# blinds_v60.net
KiCad netlist of a schematic drawn in EAGLE
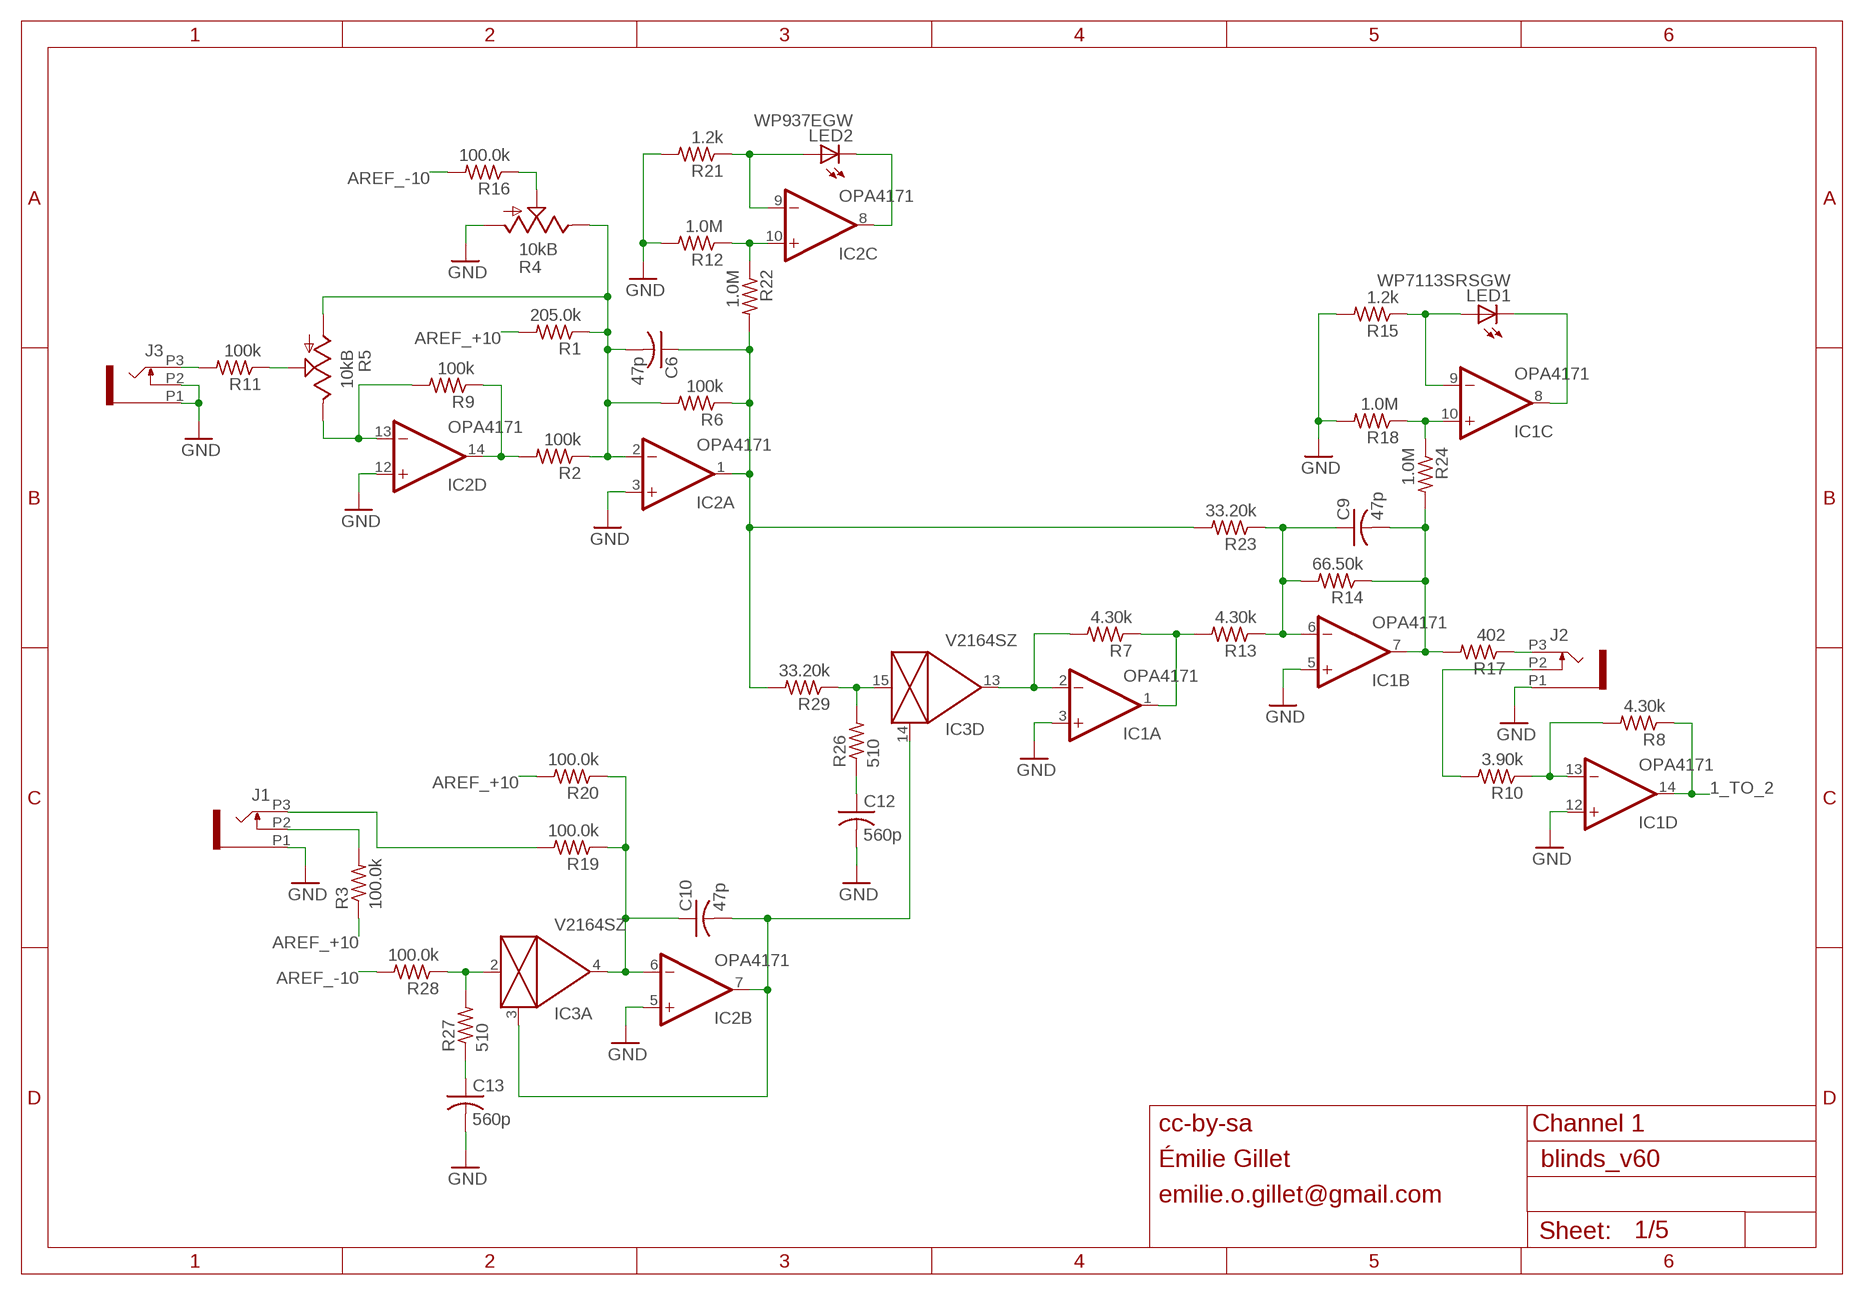
[diagram p0: schematic, sheet 1]
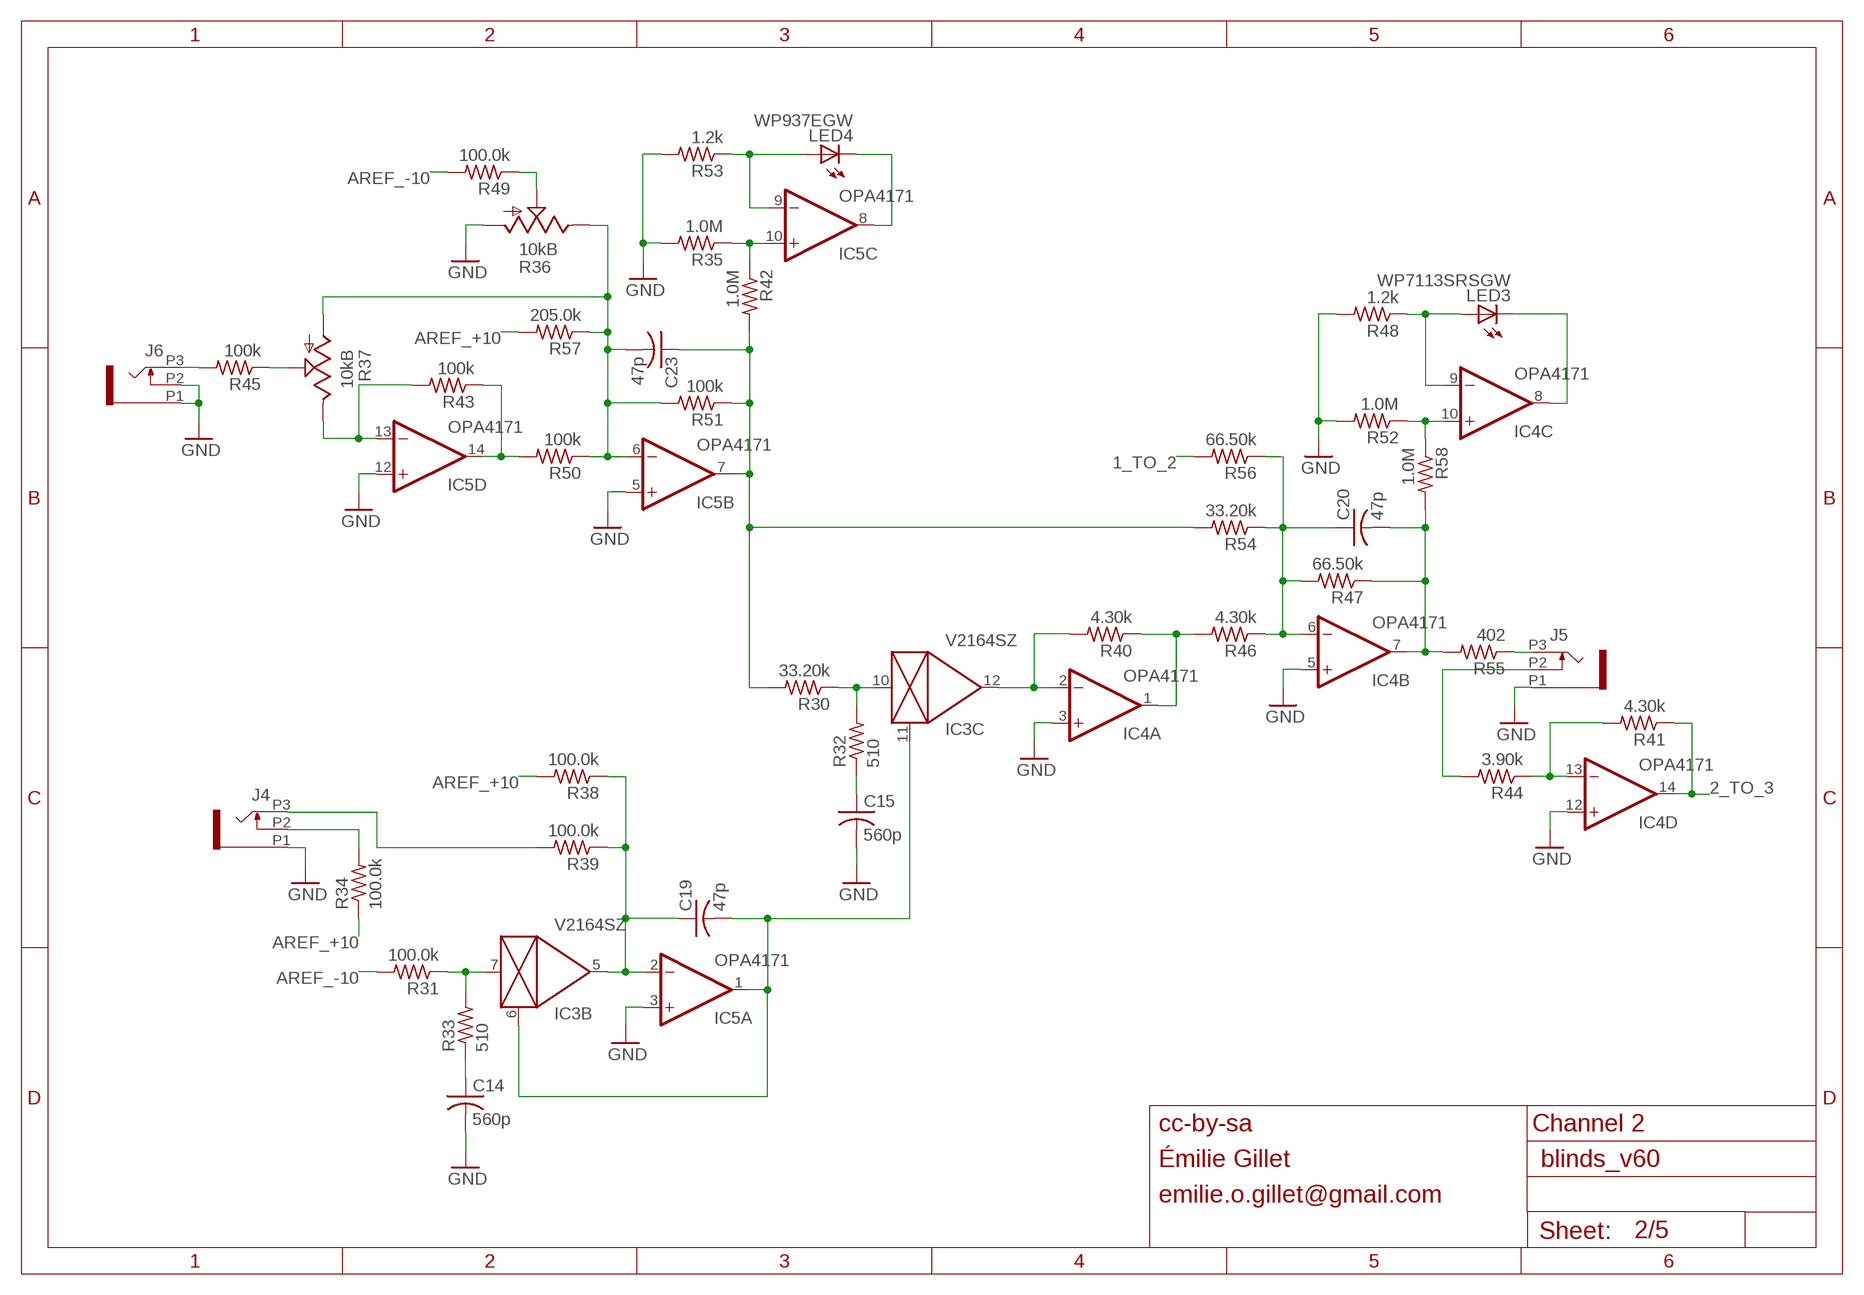
[diagram p1: schematic, sheet 2]
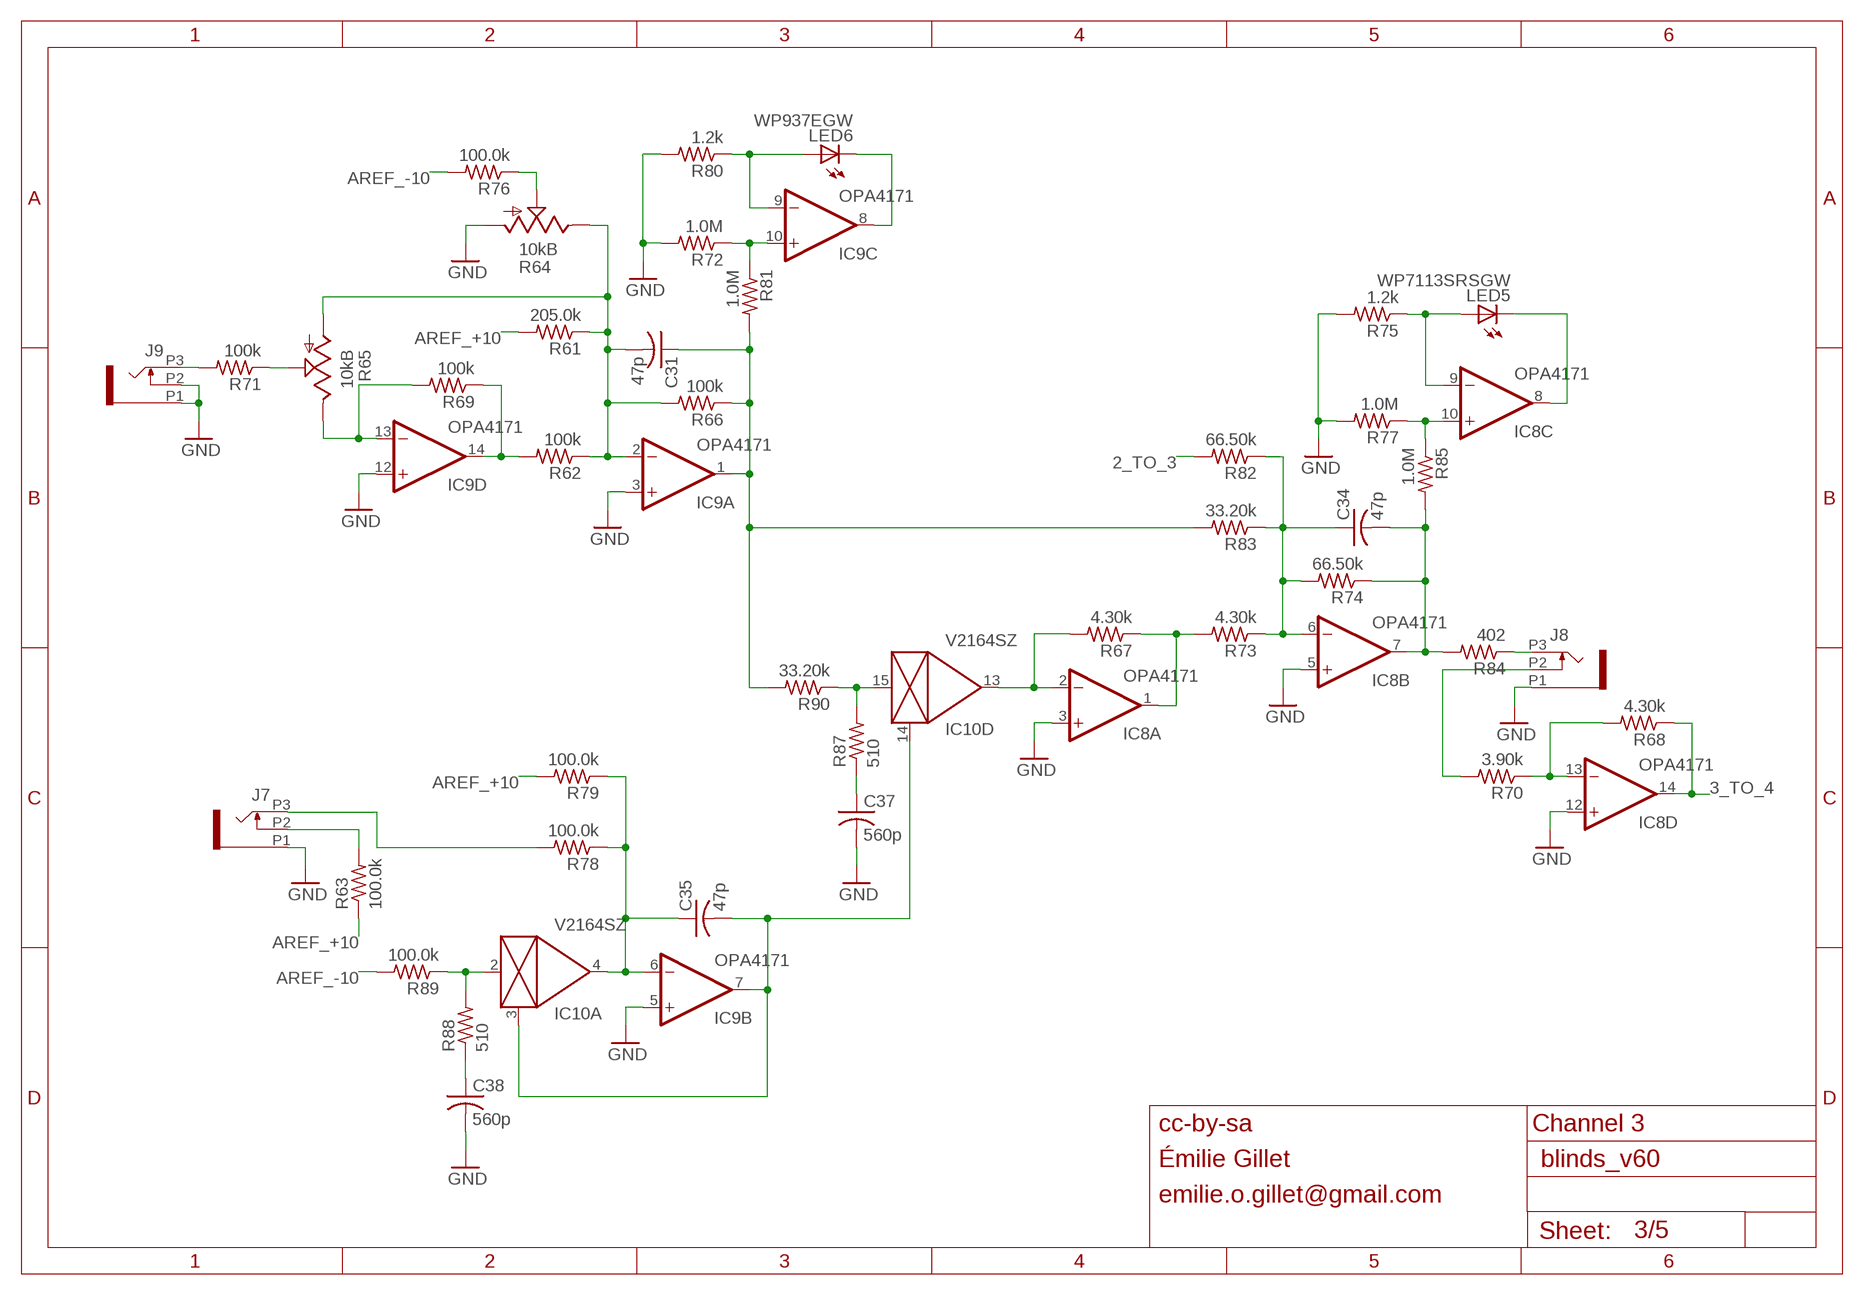
[diagram p2: schematic, sheet 3]
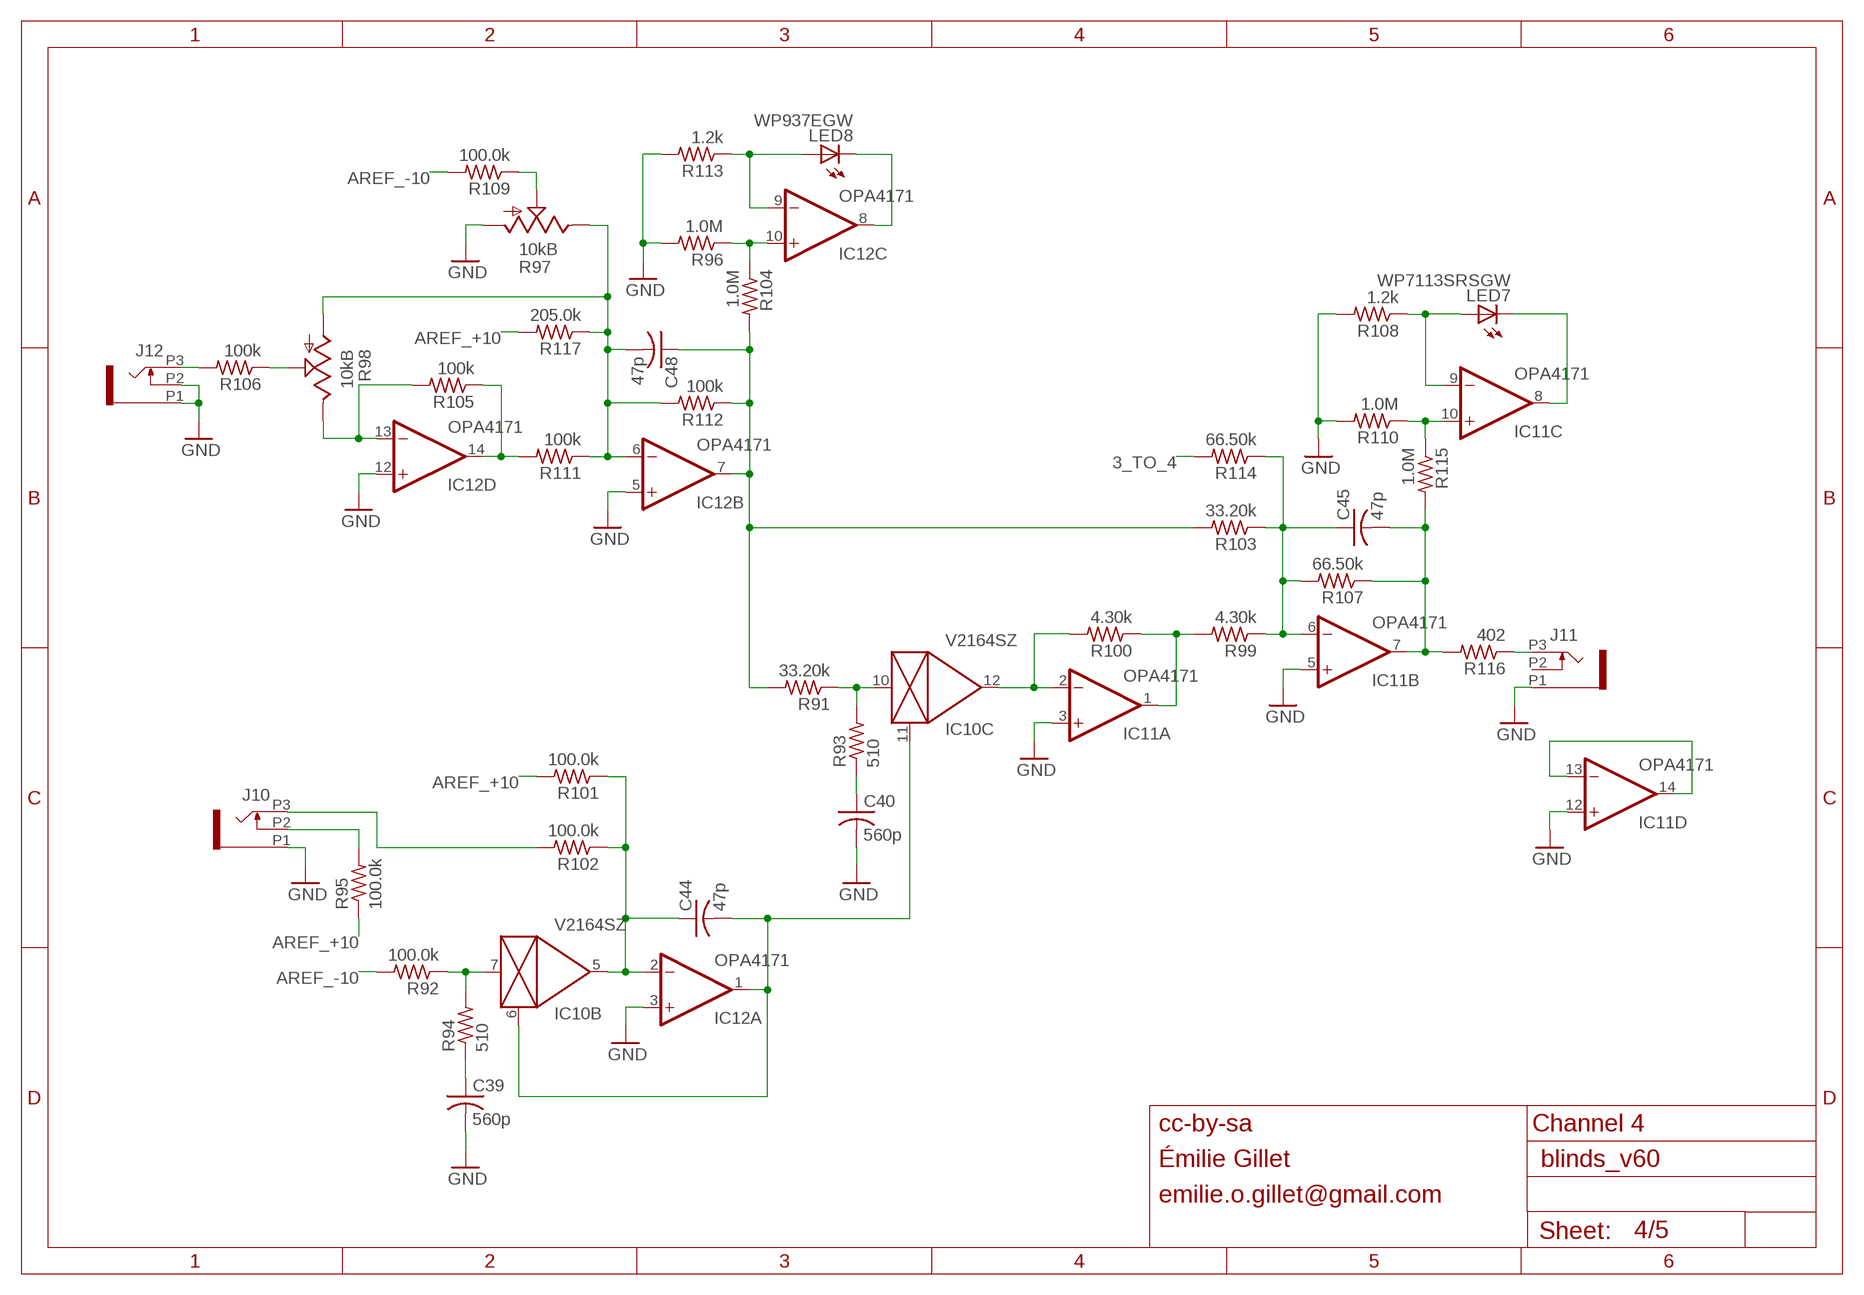
[diagram p3: schematic, sheet 4]
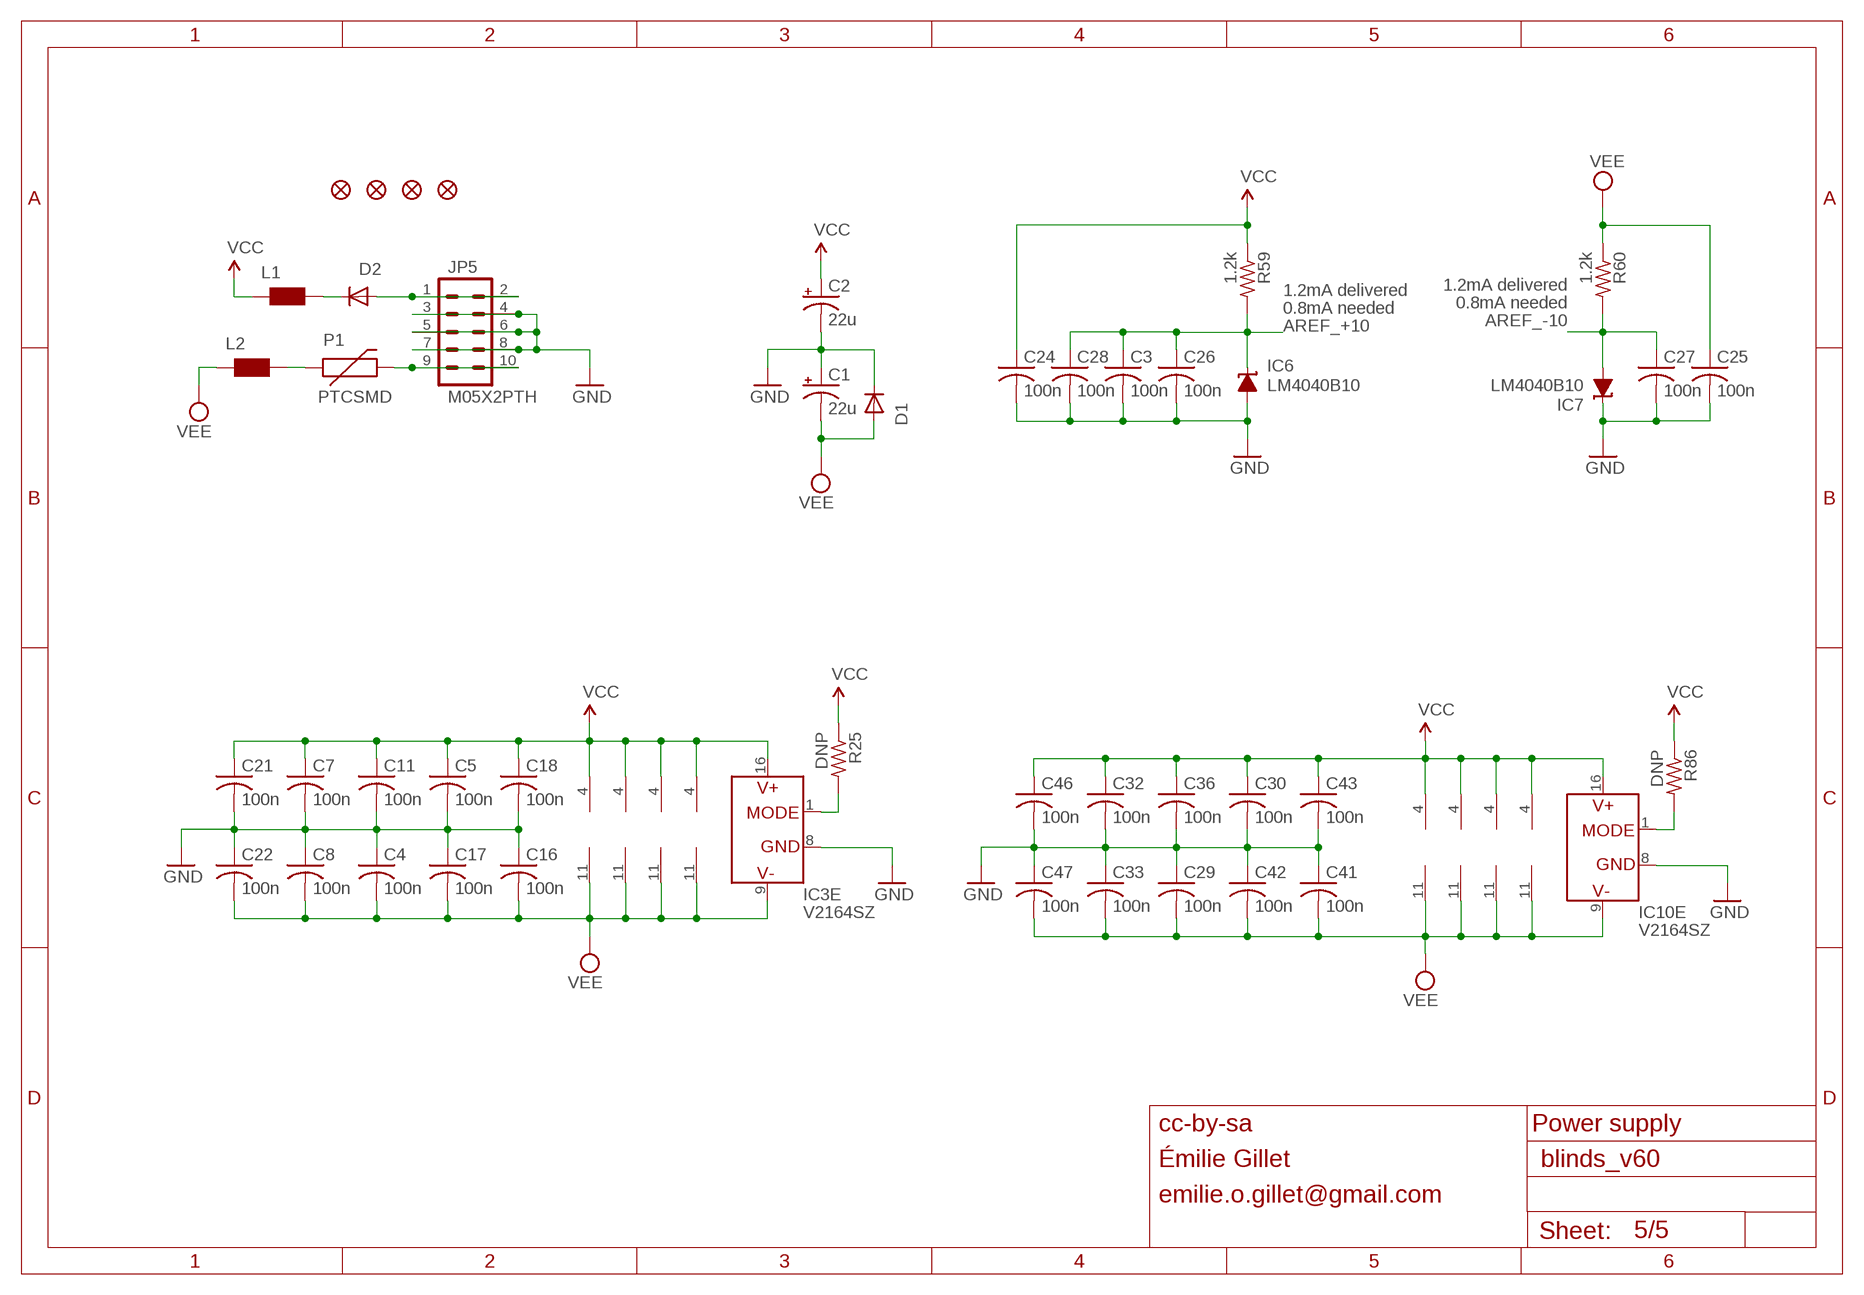
[diagram p4: schematic, sheet 5]

(export (version "E")
  (design (tool "Eeschema 10.0.6"))
  (components
    (comp (ref "C1")
      (value "22u")
      (footprint "eagle-import:PANASONIC_C")
      (libsource (lib "eagle-import") (part "CPOL-USC"))
    )
    (comp (ref "C2")
      (value "22u")
      (footprint "eagle-import:PANASONIC_C")
      (libsource (lib "eagle-import") (part "CPOL-USC"))
    )
    (comp (ref "C3")
      (value "100n")
      (footprint "eagle-import:C0603")
      (libsource (lib "eagle-import") (part "C-USC0603"))
    )
    (comp (ref "C4")
      (value "100n")
      (footprint "eagle-import:C0603")
      (libsource (lib "eagle-import") (part "C-USC0603"))
    )
    (comp (ref "C5")
      (value "100n")
      (footprint "eagle-import:C0603")
      (libsource (lib "eagle-import") (part "C-USC0603"))
    )
    (comp (ref "C7")
      (value "100n")
      (footprint "eagle-import:C0603")
      (libsource (lib "eagle-import") (part "C-USC0603"))
    )
    (comp (ref "C8")
      (value "100n")
      (footprint "eagle-import:C0603")
      (libsource (lib "eagle-import") (part "C-USC0603"))
    )
    (comp (ref "C11")
      (value "100n")
      (footprint "eagle-import:C0603")
      (libsource (lib "eagle-import") (part "C-USC0603"))
    )
    (comp (ref "C16")
      (value "100n")
      (footprint "eagle-import:C0603")
      (libsource (lib "eagle-import") (part "C-USC0603"))
    )
    (comp (ref "C17")
      (value "100n")
      (footprint "eagle-import:C0603")
      (libsource (lib "eagle-import") (part "C-USC0603"))
    )
    (comp (ref "C18")
      (value "100n")
      (footprint "eagle-import:C0603")
      (libsource (lib "eagle-import") (part "C-USC0603"))
    )
    (comp (ref "C21")
      (value "100n")
      (footprint "eagle-import:C0603")
      (libsource (lib "eagle-import") (part "C-USC0603"))
    )
    (comp (ref "C22")
      (value "100n")
      (footprint "eagle-import:C0603")
      (libsource (lib "eagle-import") (part "C-USC0603"))
    )
    (comp (ref "C24")
      (value "100n")
      (footprint "eagle-import:C0603")
      (libsource (lib "eagle-import") (part "C-USC0603"))
    )
    (comp (ref "C25")
      (value "100n")
      (footprint "eagle-import:C0603")
      (libsource (lib "eagle-import") (part "C-USC0603"))
    )
    (comp (ref "C26")
      (value "100n")
      (footprint "eagle-import:C0603")
      (libsource (lib "eagle-import") (part "C-USC0603"))
    )
    (comp (ref "C27")
      (value "100n")
      (footprint "eagle-import:C0603")
      (libsource (lib "eagle-import") (part "C-USC0603"))
    )
    (comp (ref "C28")
      (value "100n")
      (footprint "eagle-import:C0603")
      (libsource (lib "eagle-import") (part "C-USC0603"))
    )
    (comp (ref "C29")
      (value "100n")
      (footprint "eagle-import:C0603")
      (libsource (lib "eagle-import") (part "C-USC0603"))
    )
    (comp (ref "C30")
      (value "100n")
      (footprint "eagle-import:C0603")
      (libsource (lib "eagle-import") (part "C-USC0603"))
    )
    (comp (ref "C32")
      (value "100n")
      (footprint "eagle-import:C0603")
      (libsource (lib "eagle-import") (part "C-USC0603"))
    )
    (comp (ref "C33")
      (value "100n")
      (footprint "eagle-import:C0603")
      (libsource (lib "eagle-import") (part "C-USC0603"))
    )
    (comp (ref "C36")
      (value "100n")
      (footprint "eagle-import:C0603")
      (libsource (lib "eagle-import") (part "C-USC0603"))
    )
    (comp (ref "C41")
      (value "100n")
      (footprint "eagle-import:C0603")
      (libsource (lib "eagle-import") (part "C-USC0603"))
    )
    (comp (ref "C42")
      (value "100n")
      (footprint "eagle-import:C0603")
      (libsource (lib "eagle-import") (part "C-USC0603"))
    )
    (comp (ref "C43")
      (value "100n")
      (footprint "eagle-import:C0603")
      (libsource (lib "eagle-import") (part "C-USC0603"))
    )
    (comp (ref "C46")
      (value "100n")
      (footprint "eagle-import:C0603")
      (libsource (lib "eagle-import") (part "C-USC0603"))
    )
    (comp (ref "C47")
      (value "100n")
      (footprint "eagle-import:C0603")
      (libsource (lib "eagle-import") (part "C-USC0603"))
    )
    (comp (ref "D1")
      (value "1N5819HW")
      (footprint "eagle-import:SOD123")
      (libsource (lib "eagle-import") (part "DIODE-SOD123"))
    )
    (comp (ref "D2")
      (value "1N5819HW")
      (footprint "eagle-import:SOD123")
      (libsource (lib "eagle-import") (part "DIODE-SOD123"))
    )
    (comp (ref "IC1")
      (value "OPA4171")
      (footprint "eagle-import:TSSOP14")
      (libsource (lib "eagle-import") (part "TL074PW"))
    )
    (comp (ref "IC2")
      (value "OPA4171")
      (footprint "eagle-import:TSSOP14")
      (libsource (lib "eagle-import") (part "TL074PW"))
    )
    (comp (ref "IC3")
      (value "V2164SZ")
      (footprint "eagle-import:SOIC16N")
      (libsource (lib "eagle-import") (part "SSM2164S"))
    )
    (comp (ref "IC4")
      (value "OPA4171")
      (footprint "eagle-import:TSSOP14")
      (libsource (lib "eagle-import") (part "TL074PW"))
    )
    (comp (ref "IC5")
      (value "OPA4171")
      (footprint "eagle-import:TSSOP14")
      (libsource (lib "eagle-import") (part "TL074PW"))
    )
    (comp (ref "IC6")
      (value "LM4040B10")
      (footprint "eagle-import:DBZ_R-PDSO-G3")
      (libsource (lib "eagle-import") (part "LM4041DBZB12"))
    )
    (comp (ref "IC7")
      (value "LM4040B10")
      (footprint "eagle-import:DBZ_R-PDSO-G3")
      (libsource (lib "eagle-import") (part "LM4041DBZB12"))
    )
    (comp (ref "IC8")
      (value "OPA4171")
      (footprint "eagle-import:TSSOP14")
      (libsource (lib "eagle-import") (part "TL074PW"))
    )
    (comp (ref "IC9")
      (value "OPA4171")
      (footprint "eagle-import:TSSOP14")
      (libsource (lib "eagle-import") (part "TL074PW"))
    )
    (comp (ref "IC10")
      (value "V2164SZ")
      (footprint "eagle-import:SOIC16N")
      (libsource (lib "eagle-import") (part "SSM2164S"))
    )
    (comp (ref "IC11")
      (value "OPA4171")
      (footprint "eagle-import:TSSOP14")
      (libsource (lib "eagle-import") (part "TL074PW"))
    )
    (comp (ref "IC12")
      (value "OPA4171")
      (footprint "eagle-import:TSSOP14")
      (libsource (lib "eagle-import") (part "TL074PW"))
    )
    (comp (ref "JP1")
      (value "FIDUCIAL1X2")
      (footprint "eagle-import:FIDUCIAL-1X2")
      (libsource (lib "eagle-import") (part "FIDUCIAL1X2"))
    )
    (comp (ref "JP2")
      (value "FIDUCIAL1X2")
      (footprint "eagle-import:FIDUCIAL-1X2")
      (libsource (lib "eagle-import") (part "FIDUCIAL1X2"))
    )
    (comp (ref "JP3")
      (value "FIDUCIAL1X2")
      (footprint "eagle-import:FIDUCIAL-1X2")
      (libsource (lib "eagle-import") (part "FIDUCIAL1X2"))
    )
    (comp (ref "JP4")
      (value "FIDUCIAL1X2")
      (footprint "eagle-import:FIDUCIAL-1X2")
      (libsource (lib "eagle-import") (part "FIDUCIAL1X2"))
    )
    (comp (ref "JP5")
      (value "M05X2PTH")
      (footprint "eagle-import:AVR_ICSP")
      (libsource (lib "eagle-import") (part "M05X2PTH"))
    )
    (comp (ref "L1")
      (value "WE-CBF_0603")
      (footprint "eagle-import:0603")
      (libsource (lib "eagle-import") (part "WE-CBF_0603"))
    )
    (comp (ref "L2")
      (value "WE-CBF_0603")
      (footprint "eagle-import:0603")
      (libsource (lib "eagle-import") (part "WE-CBF_0603"))
    )
    (comp (ref "P1")
      (value "PTCSMD")
      (footprint "eagle-import:PTC-1206")
      (libsource (lib "eagle-import") (part "PTCSMD"))
    )
    (comp (ref "R25")
      (value "DNP")
      (footprint "eagle-import:R0603")
      (libsource (lib "eagle-import") (part "R-US_R0603"))
    )
    (comp (ref "R59")
      (value "1.2k")
      (footprint "eagle-import:R0603")
      (libsource (lib "eagle-import") (part "R-US_R0603"))
    )
    (comp (ref "R60")
      (value "1.2k")
      (footprint "eagle-import:R0603")
      (libsource (lib "eagle-import") (part "R-US_R0603"))
    )
    (comp (ref "R86")
      (value "DNP")
      (footprint "eagle-import:R0603")
      (libsource (lib "eagle-import") (part "R-US_R0603"))
    )
    (comp (ref "C31")
      (value "47p")
      (footprint "eagle-import:C0603")
      (libsource (lib "eagle-import") (part "C-USC0603"))
    )
    (comp (ref "C34")
      (value "47p")
      (footprint "eagle-import:C0603")
      (libsource (lib "eagle-import") (part "C-USC0603"))
    )
    (comp (ref "C35")
      (value "47p")
      (footprint "eagle-import:C0603")
      (libsource (lib "eagle-import") (part "C-USC0603"))
    )
    (comp (ref "C37")
      (value "560p")
      (footprint "eagle-import:C0603")
      (libsource (lib "eagle-import") (part "C-USC0603"))
    )
    (comp (ref "C38")
      (value "560p")
      (footprint "eagle-import:C0603")
      (libsource (lib "eagle-import") (part "C-USC0603"))
    )
    (comp (ref "J7")
      (value "PJ301_THONKICONN6")
      (footprint "eagle-import:WQP_PJ_301M6")
      (libsource (lib "eagle-import") (part "PJ301_THONKICONN6"))
    )
    (comp (ref "J8")
      (value "PJ301_THONKICONN6")
      (footprint "eagle-import:WQP_PJ_301M6")
      (libsource (lib "eagle-import") (part "PJ301_THONKICONN6"))
    )
    (comp (ref "J9")
      (value "PJ301_THONKICONN6")
      (footprint "eagle-import:WQP_PJ_301M6")
      (libsource (lib "eagle-import") (part "PJ301_THONKICONN6"))
    )
    (comp (ref "LED5")
      (value "WP7113SRSGW")
      (footprint "eagle-import:LED5MM")
      (libsource (lib "eagle-import") (part "LED5MM"))
    )
    (comp (ref "LED6")
      (value "WP937EGW")
      (footprint "eagle-import:LED3MM")
      (libsource (lib "eagle-import") (part "LED3MM"))
    )
    (comp (ref "R61")
      (value "205.0k")
      (footprint "eagle-import:R0603")
      (libsource (lib "eagle-import") (part "R-US_R0603"))
    )
    (comp (ref "R62")
      (value "100k")
      (footprint "eagle-import:R0603")
      (libsource (lib "eagle-import") (part "R-US_R0603"))
    )
    (comp (ref "R63")
      (value "100.0k")
      (footprint "eagle-import:R0603")
      (libsource (lib "eagle-import") (part "R-US_R0603"))
    )
    (comp (ref "R64")
      (value "10kB")
      (footprint "eagle-import:ALPS_POT_VERTICAL_PS")
      (libsource (lib "eagle-import") (part "POT_USVERTICAL_PS"))
    )
    (comp (ref "R65")
      (value "10kB")
      (footprint "eagle-import:ALPS_POT_VERTICAL")
      (libsource (lib "eagle-import") (part "POT_USVERTICAL"))
    )
    (comp (ref "R66")
      (value "100k")
      (footprint "eagle-import:R0603")
      (libsource (lib "eagle-import") (part "R-US_R0603"))
    )
    (comp (ref "R67")
      (value "4.30k")
      (footprint "eagle-import:R0603")
      (libsource (lib "eagle-import") (part "R-US_R0603"))
    )
    (comp (ref "R68")
      (value "4.30k")
      (footprint "eagle-import:R0603")
      (libsource (lib "eagle-import") (part "R-US_R0603"))
    )
    (comp (ref "R69")
      (value "100k")
      (footprint "eagle-import:R0603")
      (libsource (lib "eagle-import") (part "R-US_R0603"))
    )
    (comp (ref "R70")
      (value "3.90k")
      (footprint "eagle-import:R0603")
      (libsource (lib "eagle-import") (part "R-US_R0603"))
    )
    (comp (ref "R71")
      (value "100k")
      (footprint "eagle-import:R0603")
      (libsource (lib "eagle-import") (part "R-US_R0603"))
    )
    (comp (ref "R72")
      (value "1.0M")
      (footprint "eagle-import:R0603")
      (libsource (lib "eagle-import") (part "R-US_R0603"))
    )
    (comp (ref "R73")
      (value "4.30k")
      (footprint "eagle-import:R0603")
      (libsource (lib "eagle-import") (part "R-US_R0603"))
    )
    (comp (ref "R74")
      (value "66.50k")
      (footprint "eagle-import:R0603")
      (libsource (lib "eagle-import") (part "R-US_R0603"))
    )
    (comp (ref "R75")
      (value "1.2k")
      (footprint "eagle-import:R0603")
      (libsource (lib "eagle-import") (part "R-US_R0603"))
    )
    (comp (ref "R76")
      (value "100.0k")
      (footprint "eagle-import:R0603")
      (libsource (lib "eagle-import") (part "R-US_R0603"))
    )
    (comp (ref "R77")
      (value "1.0M")
      (footprint "eagle-import:R0603")
      (libsource (lib "eagle-import") (part "R-US_R0603"))
    )
    (comp (ref "R78")
      (value "100.0k")
      (footprint "eagle-import:R0603")
      (libsource (lib "eagle-import") (part "R-US_R0603"))
    )
    (comp (ref "R79")
      (value "100.0k")
      (footprint "eagle-import:R0603")
      (libsource (lib "eagle-import") (part "R-US_R0603"))
    )
    (comp (ref "R80")
      (value "1.2k")
      (footprint "eagle-import:R0603")
      (libsource (lib "eagle-import") (part "R-US_R0603"))
    )
    (comp (ref "R81")
      (value "1.0M")
      (footprint "eagle-import:R0603")
      (libsource (lib "eagle-import") (part "R-US_R0603"))
    )
    (comp (ref "R82")
      (value "66.50k")
      (footprint "eagle-import:R0603")
      (libsource (lib "eagle-import") (part "R-US_R0603"))
    )
    (comp (ref "R83")
      (value "33.20k")
      (footprint "eagle-import:R0603")
      (libsource (lib "eagle-import") (part "R-US_R0603"))
    )
    (comp (ref "R84")
      (value "402")
      (footprint "eagle-import:R0603")
      (libsource (lib "eagle-import") (part "R-US_R0603"))
    )
    (comp (ref "R85")
      (value "1.0M")
      (footprint "eagle-import:R0603")
      (libsource (lib "eagle-import") (part "R-US_R0603"))
    )
    (comp (ref "R87")
      (value "510")
      (footprint "eagle-import:R0603")
      (libsource (lib "eagle-import") (part "R-US_R0603"))
    )
    (comp (ref "R88")
      (value "510")
      (footprint "eagle-import:R0603")
      (libsource (lib "eagle-import") (part "R-US_R0603"))
    )
    (comp (ref "R89")
      (value "100.0k")
      (footprint "eagle-import:R0603")
      (libsource (lib "eagle-import") (part "R-US_R0603"))
    )
    (comp (ref "R90")
      (value "33.20k")
      (footprint "eagle-import:R0603")
      (libsource (lib "eagle-import") (part "R-US_R0603"))
    )
    (comp (ref "C39")
      (value "560p")
      (footprint "eagle-import:C0603")
      (libsource (lib "eagle-import") (part "C-USC0603"))
    )
    (comp (ref "C40")
      (value "560p")
      (footprint "eagle-import:C0603")
      (libsource (lib "eagle-import") (part "C-USC0603"))
    )
    (comp (ref "C44")
      (value "47p")
      (footprint "eagle-import:C0603")
      (libsource (lib "eagle-import") (part "C-USC0603"))
    )
    (comp (ref "C45")
      (value "47p")
      (footprint "eagle-import:C0603")
      (libsource (lib "eagle-import") (part "C-USC0603"))
    )
    (comp (ref "C48")
      (value "47p")
      (footprint "eagle-import:C0603")
      (libsource (lib "eagle-import") (part "C-USC0603"))
    )
    (comp (ref "J10")
      (value "PJ301_THONKICONN6")
      (footprint "eagle-import:WQP_PJ_301M6")
      (libsource (lib "eagle-import") (part "PJ301_THONKICONN6"))
    )
    (comp (ref "J11")
      (value "PJ301_THONKICONN6")
      (footprint "eagle-import:WQP_PJ_301M6")
      (libsource (lib "eagle-import") (part "PJ301_THONKICONN6"))
    )
    (comp (ref "J12")
      (value "PJ301_THONKICONN6")
      (footprint "eagle-import:WQP_PJ_301M6")
      (libsource (lib "eagle-import") (part "PJ301_THONKICONN6"))
    )
    (comp (ref "LED7")
      (value "WP7113SRSGW")
      (footprint "eagle-import:LED5MM")
      (libsource (lib "eagle-import") (part "LED5MM"))
    )
    (comp (ref "LED8")
      (value "WP937EGW")
      (footprint "eagle-import:LED3MM")
      (libsource (lib "eagle-import") (part "LED3MM"))
    )
    (comp (ref "R91")
      (value "33.20k")
      (footprint "eagle-import:R0603")
      (libsource (lib "eagle-import") (part "R-US_R0603"))
    )
    (comp (ref "R92")
      (value "100.0k")
      (footprint "eagle-import:R0603")
      (libsource (lib "eagle-import") (part "R-US_R0603"))
    )
    (comp (ref "R93")
      (value "510")
      (footprint "eagle-import:R0603")
      (libsource (lib "eagle-import") (part "R-US_R0603"))
    )
    (comp (ref "R94")
      (value "510")
      (footprint "eagle-import:R0603")
      (libsource (lib "eagle-import") (part "R-US_R0603"))
    )
    (comp (ref "R95")
      (value "100.0k")
      (footprint "eagle-import:R0603")
      (libsource (lib "eagle-import") (part "R-US_R0603"))
    )
    (comp (ref "R96")
      (value "1.0M")
      (footprint "eagle-import:R0603")
      (libsource (lib "eagle-import") (part "R-US_R0603"))
    )
    (comp (ref "R97")
      (value "10kB")
      (footprint "eagle-import:ALPS_POT_VERTICAL_PS")
      (libsource (lib "eagle-import") (part "POT_USVERTICAL_PS"))
    )
    (comp (ref "R98")
      (value "10kB")
      (footprint "eagle-import:ALPS_POT_VERTICAL")
      (libsource (lib "eagle-import") (part "POT_USVERTICAL"))
    )
    (comp (ref "R99")
      (value "4.30k")
      (footprint "eagle-import:R0603")
      (libsource (lib "eagle-import") (part "R-US_R0603"))
    )
    (comp (ref "R100")
      (value "4.30k")
      (footprint "eagle-import:R0603")
      (libsource (lib "eagle-import") (part "R-US_R0603"))
    )
    (comp (ref "R101")
      (value "100.0k")
      (footprint "eagle-import:R0603")
      (libsource (lib "eagle-import") (part "R-US_R0603"))
    )
    (comp (ref "R102")
      (value "100.0k")
      (footprint "eagle-import:R0603")
      (libsource (lib "eagle-import") (part "R-US_R0603"))
    )
    (comp (ref "R103")
      (value "33.20k")
      (footprint "eagle-import:R0603")
      (libsource (lib "eagle-import") (part "R-US_R0603"))
    )
    (comp (ref "R104")
      (value "1.0M")
      (footprint "eagle-import:R0603")
      (libsource (lib "eagle-import") (part "R-US_R0603"))
    )
    (comp (ref "R105")
      (value "100k")
      (footprint "eagle-import:R0603")
      (libsource (lib "eagle-import") (part "R-US_R0603"))
    )
    (comp (ref "R106")
      (value "100k")
      (footprint "eagle-import:R0603")
      (libsource (lib "eagle-import") (part "R-US_R0603"))
    )
    (comp (ref "R107")
      (value "66.50k")
      (footprint "eagle-import:R0603")
      (libsource (lib "eagle-import") (part "R-US_R0603"))
    )
    (comp (ref "R108")
      (value "1.2k")
      (footprint "eagle-import:R0603")
      (libsource (lib "eagle-import") (part "R-US_R0603"))
    )
    (comp (ref "R109")
      (value "100.0k")
      (footprint "eagle-import:R0603")
      (libsource (lib "eagle-import") (part "R-US_R0603"))
    )
    (comp (ref "R110")
      (value "1.0M")
      (footprint "eagle-import:R0603")
      (libsource (lib "eagle-import") (part "R-US_R0603"))
    )
    (comp (ref "R111")
      (value "100k")
      (footprint "eagle-import:R0603")
      (libsource (lib "eagle-import") (part "R-US_R0603"))
    )
    (comp (ref "R112")
      (value "100k")
      (footprint "eagle-import:R0603")
      (libsource (lib "eagle-import") (part "R-US_R0603"))
    )
    (comp (ref "R113")
      (value "1.2k")
      (footprint "eagle-import:R0603")
      (libsource (lib "eagle-import") (part "R-US_R0603"))
    )
    (comp (ref "R114")
      (value "66.50k")
      (footprint "eagle-import:R0603")
      (libsource (lib "eagle-import") (part "R-US_R0603"))
    )
    (comp (ref "R115")
      (value "1.0M")
      (footprint "eagle-import:R0603")
      (libsource (lib "eagle-import") (part "R-US_R0603"))
    )
    (comp (ref "R116")
      (value "402")
      (footprint "eagle-import:R0603")
      (libsource (lib "eagle-import") (part "R-US_R0603"))
    )
    (comp (ref "R117")
      (value "205.0k")
      (footprint "eagle-import:R0603")
      (libsource (lib "eagle-import") (part "R-US_R0603"))
    )
    (comp (ref "C14")
      (value "560p")
      (footprint "eagle-import:C0603")
      (libsource (lib "eagle-import") (part "C-USC0603"))
    )
    (comp (ref "C15")
      (value "560p")
      (footprint "eagle-import:C0603")
      (libsource (lib "eagle-import") (part "C-USC0603"))
    )
    (comp (ref "C19")
      (value "47p")
      (footprint "eagle-import:C0603")
      (libsource (lib "eagle-import") (part "C-USC0603"))
    )
    (comp (ref "C20")
      (value "47p")
      (footprint "eagle-import:C0603")
      (libsource (lib "eagle-import") (part "C-USC0603"))
    )
    (comp (ref "C23")
      (value "47p")
      (footprint "eagle-import:C0603")
      (libsource (lib "eagle-import") (part "C-USC0603"))
    )
    (comp (ref "J4")
      (value "PJ301_THONKICONN6")
      (footprint "eagle-import:WQP_PJ_301M6")
      (libsource (lib "eagle-import") (part "PJ301_THONKICONN6"))
    )
    (comp (ref "J5")
      (value "PJ301_THONKICONN6")
      (footprint "eagle-import:WQP_PJ_301M6")
      (libsource (lib "eagle-import") (part "PJ301_THONKICONN6"))
    )
    (comp (ref "J6")
      (value "PJ301_THONKICONN6")
      (footprint "eagle-import:WQP_PJ_301M6")
      (libsource (lib "eagle-import") (part "PJ301_THONKICONN6"))
    )
    (comp (ref "LED3")
      (value "WP7113SRSGW")
      (footprint "eagle-import:LED5MM")
      (libsource (lib "eagle-import") (part "LED5MM"))
    )
    (comp (ref "LED4")
      (value "WP937EGW")
      (footprint "eagle-import:LED3MM")
      (libsource (lib "eagle-import") (part "LED3MM"))
    )
    (comp (ref "R30")
      (value "33.20k")
      (footprint "eagle-import:R0603")
      (libsource (lib "eagle-import") (part "R-US_R0603"))
    )
    (comp (ref "R31")
      (value "100.0k")
      (footprint "eagle-import:R0603")
      (libsource (lib "eagle-import") (part "R-US_R0603"))
    )
    (comp (ref "R32")
      (value "510")
      (footprint "eagle-import:R0603")
      (libsource (lib "eagle-import") (part "R-US_R0603"))
    )
    (comp (ref "R33")
      (value "510")
      (footprint "eagle-import:R0603")
      (libsource (lib "eagle-import") (part "R-US_R0603"))
    )
    (comp (ref "R34")
      (value "100.0k")
      (footprint "eagle-import:R0603")
      (libsource (lib "eagle-import") (part "R-US_R0603"))
    )
    (comp (ref "R35")
      (value "1.0M")
      (footprint "eagle-import:R0603")
      (libsource (lib "eagle-import") (part "R-US_R0603"))
    )
    (comp (ref "R36")
      (value "10kB")
      (footprint "eagle-import:ALPS_POT_VERTICAL_PS")
      (libsource (lib "eagle-import") (part "POT_USVERTICAL_PS"))
    )
    (comp (ref "R37")
      (value "10kB")
      (footprint "eagle-import:ALPS_POT_VERTICAL")
      (libsource (lib "eagle-import") (part "POT_USVERTICAL"))
    )
    (comp (ref "R38")
      (value "100.0k")
      (footprint "eagle-import:R0603")
      (libsource (lib "eagle-import") (part "R-US_R0603"))
    )
    (comp (ref "R39")
      (value "100.0k")
      (footprint "eagle-import:R0603")
      (libsource (lib "eagle-import") (part "R-US_R0603"))
    )
    (comp (ref "R40")
      (value "4.30k")
      (footprint "eagle-import:R0603")
      (libsource (lib "eagle-import") (part "R-US_R0603"))
    )
    (comp (ref "R41")
      (value "4.30k")
      (footprint "eagle-import:R0603")
      (libsource (lib "eagle-import") (part "R-US_R0603"))
    )
    (comp (ref "R42")
      (value "1.0M")
      (footprint "eagle-import:R0603")
      (libsource (lib "eagle-import") (part "R-US_R0603"))
    )
    (comp (ref "R43")
      (value "100k")
      (footprint "eagle-import:R0603")
      (libsource (lib "eagle-import") (part "R-US_R0603"))
    )
    (comp (ref "R44")
      (value "3.90k")
      (footprint "eagle-import:R0603")
      (libsource (lib "eagle-import") (part "R-US_R0603"))
    )
    (comp (ref "R45")
      (value "100k")
      (footprint "eagle-import:R0603")
      (libsource (lib "eagle-import") (part "R-US_R0603"))
    )
    (comp (ref "R46")
      (value "4.30k")
      (footprint "eagle-import:R0603")
      (libsource (lib "eagle-import") (part "R-US_R0603"))
    )
    (comp (ref "R47")
      (value "66.50k")
      (footprint "eagle-import:R0603")
      (libsource (lib "eagle-import") (part "R-US_R0603"))
    )
    (comp (ref "R48")
      (value "1.2k")
      (footprint "eagle-import:R0603")
      (libsource (lib "eagle-import") (part "R-US_R0603"))
    )
    (comp (ref "R49")
      (value "100.0k")
      (footprint "eagle-import:R0603")
      (libsource (lib "eagle-import") (part "R-US_R0603"))
    )
    (comp (ref "R50")
      (value "100k")
      (footprint "eagle-import:R0603")
      (libsource (lib "eagle-import") (part "R-US_R0603"))
    )
    (comp (ref "R51")
      (value "100k")
      (footprint "eagle-import:R0603")
      (libsource (lib "eagle-import") (part "R-US_R0603"))
    )
    (comp (ref "R52")
      (value "1.0M")
      (footprint "eagle-import:R0603")
      (libsource (lib "eagle-import") (part "R-US_R0603"))
    )
    (comp (ref "R53")
      (value "1.2k")
      (footprint "eagle-import:R0603")
      (libsource (lib "eagle-import") (part "R-US_R0603"))
    )
    (comp (ref "R54")
      (value "33.20k")
      (footprint "eagle-import:R0603")
      (libsource (lib "eagle-import") (part "R-US_R0603"))
    )
    (comp (ref "R55")
      (value "402")
      (footprint "eagle-import:R0603")
      (libsource (lib "eagle-import") (part "R-US_R0603"))
    )
    (comp (ref "R56")
      (value "66.50k")
      (footprint "eagle-import:R0603")
      (libsource (lib "eagle-import") (part "R-US_R0603"))
    )
    (comp (ref "R57")
      (value "205.0k")
      (footprint "eagle-import:R0603")
      (libsource (lib "eagle-import") (part "R-US_R0603"))
    )
    (comp (ref "R58")
      (value "1.0M")
      (footprint "eagle-import:R0603")
      (libsource (lib "eagle-import") (part "R-US_R0603"))
    )
    (comp (ref "C6")
      (value "47p")
      (footprint "eagle-import:C0603")
      (libsource (lib "eagle-import") (part "C-USC0603"))
    )
    (comp (ref "C9")
      (value "47p")
      (footprint "eagle-import:C0603")
      (libsource (lib "eagle-import") (part "C-USC0603"))
    )
    (comp (ref "C10")
      (value "47p")
      (footprint "eagle-import:C0603")
      (libsource (lib "eagle-import") (part "C-USC0603"))
    )
    (comp (ref "C12")
      (value "560p")
      (footprint "eagle-import:C0603")
      (libsource (lib "eagle-import") (part "C-USC0603"))
    )
    (comp (ref "C13")
      (value "560p")
      (footprint "eagle-import:C0603")
      (libsource (lib "eagle-import") (part "C-USC0603"))
    )
    (comp (ref "J1")
      (value "PJ301_THONKICONN6")
      (footprint "eagle-import:WQP_PJ_301M6")
      (libsource (lib "eagle-import") (part "PJ301_THONKICONN6"))
    )
    (comp (ref "J2")
      (value "PJ301_THONKICONN6")
      (footprint "eagle-import:WQP_PJ_301M6")
      (libsource (lib "eagle-import") (part "PJ301_THONKICONN6"))
    )
    (comp (ref "J3")
      (value "PJ301_THONKICONN6")
      (footprint "eagle-import:WQP_PJ_301M6")
      (libsource (lib "eagle-import") (part "PJ301_THONKICONN6"))
    )
    (comp (ref "LED1")
      (value "WP7113SRSGW")
      (footprint "eagle-import:LED5MM")
      (libsource (lib "eagle-import") (part "LED5MM"))
    )
    (comp (ref "LED2")
      (value "WP937EGW")
      (footprint "eagle-import:LED3MM")
      (libsource (lib "eagle-import") (part "LED3MM"))
    )
    (comp (ref "R1")
      (value "205.0k")
      (footprint "eagle-import:R0603")
      (libsource (lib "eagle-import") (part "R-US_R0603"))
    )
    (comp (ref "R2")
      (value "100k")
      (footprint "eagle-import:R0603")
      (libsource (lib "eagle-import") (part "R-US_R0603"))
    )
    (comp (ref "R3")
      (value "100.0k")
      (footprint "eagle-import:R0603")
      (libsource (lib "eagle-import") (part "R-US_R0603"))
    )
    (comp (ref "R4")
      (value "10kB")
      (footprint "eagle-import:ALPS_POT_VERTICAL_PS")
      (libsource (lib "eagle-import") (part "POT_USVERTICAL_PS"))
    )
    (comp (ref "R5")
      (value "10kB")
      (footprint "eagle-import:ALPS_POT_VERTICAL")
      (libsource (lib "eagle-import") (part "POT_USVERTICAL"))
    )
    (comp (ref "R6")
      (value "100k")
      (footprint "eagle-import:R0603")
      (libsource (lib "eagle-import") (part "R-US_R0603"))
    )
    (comp (ref "R7")
      (value "4.30k")
      (footprint "eagle-import:R0603")
      (libsource (lib "eagle-import") (part "R-US_R0603"))
    )
    (comp (ref "R8")
      (value "4.30k")
      (footprint "eagle-import:R0603")
      (libsource (lib "eagle-import") (part "R-US_R0603"))
    )
    (comp (ref "R9")
      (value "100k")
      (footprint "eagle-import:R0603")
      (libsource (lib "eagle-import") (part "R-US_R0603"))
    )
    (comp (ref "R10")
      (value "3.90k")
      (footprint "eagle-import:R0603")
      (libsource (lib "eagle-import") (part "R-US_R0603"))
    )
    (comp (ref "R11")
      (value "100k")
      (footprint "eagle-import:R0603")
      (libsource (lib "eagle-import") (part "R-US_R0603"))
    )
    (comp (ref "R12")
      (value "1.0M")
      (footprint "eagle-import:R0603")
      (libsource (lib "eagle-import") (part "R-US_R0603"))
    )
    (comp (ref "R13")
      (value "4.30k")
      (footprint "eagle-import:R0603")
      (libsource (lib "eagle-import") (part "R-US_R0603"))
    )
    (comp (ref "R14")
      (value "66.50k")
      (footprint "eagle-import:R0603")
      (libsource (lib "eagle-import") (part "R-US_R0603"))
    )
    (comp (ref "R15")
      (value "1.2k")
      (footprint "eagle-import:R0603")
      (libsource (lib "eagle-import") (part "R-US_R0603"))
    )
    (comp (ref "R16")
      (value "100.0k")
      (footprint "eagle-import:R0603")
      (libsource (lib "eagle-import") (part "R-US_R0603"))
    )
    (comp (ref "R17")
      (value "402")
      (footprint "eagle-import:R0603")
      (libsource (lib "eagle-import") (part "R-US_R0603"))
    )
    (comp (ref "R18")
      (value "1.0M")
      (footprint "eagle-import:R0603")
      (libsource (lib "eagle-import") (part "R-US_R0603"))
    )
    (comp (ref "R19")
      (value "100.0k")
      (footprint "eagle-import:R0603")
      (libsource (lib "eagle-import") (part "R-US_R0603"))
    )
    (comp (ref "R20")
      (value "100.0k")
      (footprint "eagle-import:R0603")
      (libsource (lib "eagle-import") (part "R-US_R0603"))
    )
    (comp (ref "R21")
      (value "1.2k")
      (footprint "eagle-import:R0603")
      (libsource (lib "eagle-import") (part "R-US_R0603"))
    )
    (comp (ref "R22")
      (value "1.0M")
      (footprint "eagle-import:R0603")
      (libsource (lib "eagle-import") (part "R-US_R0603"))
    )
    (comp (ref "R23")
      (value "33.20k")
      (footprint "eagle-import:R0603")
      (libsource (lib "eagle-import") (part "R-US_R0603"))
    )
    (comp (ref "R24")
      (value "1.0M")
      (footprint "eagle-import:R0603")
      (libsource (lib "eagle-import") (part "R-US_R0603"))
    )
    (comp (ref "R26")
      (value "510")
      (footprint "eagle-import:R0603")
      (libsource (lib "eagle-import") (part "R-US_R0603"))
    )
    (comp (ref "R27")
      (value "510")
      (footprint "eagle-import:R0603")
      (libsource (lib "eagle-import") (part "R-US_R0603"))
    )
    (comp (ref "R28")
      (value "100.0k")
      (footprint "eagle-import:R0603")
      (libsource (lib "eagle-import") (part "R-US_R0603"))
    )
    (comp (ref "R29")
      (value "33.20k")
      (footprint "eagle-import:R0603")
      (libsource (lib "eagle-import") (part "R-US_R0603"))
    )
  )
  (nets
    (net (code "1") (name "1_TO_2") (class "Default")
      (node (ref "IC1") (pin "14") (pinfunction "OUT_14") (pintype "output"))
      (node (ref "R56") (pin "2") (pinfunction "2_2") (pintype "passive"))
      (node (ref "R8") (pin "1") (pinfunction "1_1") (pintype "passive"))
    )
    (net (code "2") (name "2_TO_3") (class "Default")
      (node (ref "IC4") (pin "14") (pinfunction "OUT_14") (pintype "output"))
      (node (ref "R41") (pin "1") (pinfunction "1_1") (pintype "passive"))
      (node (ref "R82") (pin "2") (pinfunction "2_2") (pintype "passive"))
    )
    (net (code "3") (name "3_TO_4") (class "Default")
      (node (ref "IC8") (pin "14") (pinfunction "OUT_14") (pintype "output"))
      (node (ref "R114") (pin "2") (pinfunction "2_2") (pintype "passive"))
      (node (ref "R68") (pin "1") (pinfunction "1_1") (pintype "passive"))
    )
    (net (code "4") (name "AREF_+10") (class "Default")
      (node (ref "C26") (pin "1") (pinfunction "1_1") (pintype "passive"))
      (node (ref "C28") (pin "1") (pinfunction "1_1") (pintype "passive"))
      (node (ref "C3") (pin "1") (pinfunction "1_1") (pintype "passive"))
      (node (ref "IC6") (pin "1") (pinfunction "C_1") (pintype "passive"))
      (node (ref "R1") (pin "2") (pinfunction "2_2") (pintype "passive"))
      (node (ref "R101") (pin "2") (pinfunction "2_2") (pintype "passive"))
      (node (ref "R117") (pin "2") (pinfunction "2_2") (pintype "passive"))
      (node (ref "R20") (pin "2") (pinfunction "2_2") (pintype "passive"))
      (node (ref "R3") (pin "1") (pinfunction "1_1") (pintype "passive"))
      (node (ref "R34") (pin "1") (pinfunction "1_1") (pintype "passive"))
      (node (ref "R38") (pin "2") (pinfunction "2_2") (pintype "passive"))
      (node (ref "R57") (pin "2") (pinfunction "2_2") (pintype "passive"))
      (node (ref "R59") (pin "2") (pinfunction "2_2") (pintype "passive"))
      (node (ref "R61") (pin "2") (pinfunction "2_2") (pintype "passive"))
      (node (ref "R63") (pin "1") (pinfunction "1_1") (pintype "passive"))
      (node (ref "R79") (pin "2") (pinfunction "2_2") (pintype "passive"))
      (node (ref "R95") (pin "1") (pinfunction "1_1") (pintype "passive"))
    )
    (net (code "5") (name "AREF_-10") (class "Default")
      (node (ref "C27") (pin "1") (pinfunction "1_1") (pintype "passive"))
      (node (ref "IC7") (pin "2") (pinfunction "A_2") (pintype "passive"))
      (node (ref "R109") (pin "2") (pinfunction "2_2") (pintype "passive"))
      (node (ref "R16") (pin "2") (pinfunction "2_2") (pintype "passive"))
      (node (ref "R28") (pin "2") (pinfunction "2_2") (pintype "passive"))
      (node (ref "R31") (pin "2") (pinfunction "2_2") (pintype "passive"))
      (node (ref "R49") (pin "2") (pinfunction "2_2") (pintype "passive"))
      (node (ref "R60") (pin "2") (pinfunction "2_2") (pintype "passive"))
      (node (ref "R76") (pin "2") (pinfunction "2_2") (pintype "passive"))
      (node (ref "R89") (pin "2") (pinfunction "2_2") (pintype "passive"))
      (node (ref "R92") (pin "2") (pinfunction "2_2") (pintype "passive"))
    )
    (net (code "6") (name "GND") (class "Default")
      (node (ref "C1") (pin "+") (pinfunction "+_+") (pintype "passive"))
      (node (ref "C11") (pin "2") (pinfunction "2_2") (pintype "passive"))
      (node (ref "C12") (pin "2") (pinfunction "2_2") (pintype "passive"))
      (node (ref "C13") (pin "2") (pinfunction "2_2") (pintype "passive"))
      (node (ref "C14") (pin "2") (pinfunction "2_2") (pintype "passive"))
      (node (ref "C15") (pin "2") (pinfunction "2_2") (pintype "passive"))
      (node (ref "C16") (pin "1") (pinfunction "1_1") (pintype "passive"))
      (node (ref "C17") (pin "1") (pinfunction "1_1") (pintype "passive"))
      (node (ref "C18") (pin "2") (pinfunction "2_2") (pintype "passive"))
      (node (ref "C2") (pin "-") (pinfunction "-_-") (pintype "passive"))
      (node (ref "C21") (pin "2") (pinfunction "2_2") (pintype "passive"))
      (node (ref "C22") (pin "1") (pinfunction "1_1") (pintype "passive"))
      (node (ref "C24") (pin "2") (pinfunction "2_2") (pintype "passive"))
      (node (ref "C25") (pin "2") (pinfunction "2_2") (pintype "passive"))
      (node (ref "C26") (pin "2") (pinfunction "2_2") (pintype "passive"))
      (node (ref "C27") (pin "2") (pinfunction "2_2") (pintype "passive"))
      (node (ref "C28") (pin "2") (pinfunction "2_2") (pintype "passive"))
      (node (ref "C29") (pin "1") (pinfunction "1_1") (pintype "passive"))
      (node (ref "C3") (pin "2") (pinfunction "2_2") (pintype "passive"))
      (node (ref "C30") (pin "2") (pinfunction "2_2") (pintype "passive"))
      (node (ref "C32") (pin "2") (pinfunction "2_2") (pintype "passive"))
      (node (ref "C33") (pin "1") (pinfunction "1_1") (pintype "passive"))
      (node (ref "C36") (pin "2") (pinfunction "2_2") (pintype "passive"))
      (node (ref "C37") (pin "2") (pinfunction "2_2") (pintype "passive"))
      (node (ref "C38") (pin "2") (pinfunction "2_2") (pintype "passive"))
      (node (ref "C39") (pin "2") (pinfunction "2_2") (pintype "passive"))
      (node (ref "C4") (pin "1") (pinfunction "1_1") (pintype "passive"))
      (node (ref "C40") (pin "2") (pinfunction "2_2") (pintype "passive"))
      (node (ref "C41") (pin "1") (pinfunction "1_1") (pintype "passive"))
      (node (ref "C42") (pin "1") (pinfunction "1_1") (pintype "passive"))
      (node (ref "C43") (pin "2") (pinfunction "2_2") (pintype "passive"))
      (node (ref "C46") (pin "2") (pinfunction "2_2") (pintype "passive"))
      (node (ref "C47") (pin "1") (pinfunction "1_1") (pintype "passive"))
      (node (ref "C5") (pin "2") (pinfunction "2_2") (pintype "passive"))
      (node (ref "C7") (pin "2") (pinfunction "2_2") (pintype "passive"))
      (node (ref "C8") (pin "1") (pinfunction "1_1") (pintype "passive"))
      (node (ref "D1") (pin "C") (pinfunction "C_C") (pintype "passive"))
      (node (ref "IC1") (pin "12") (pinfunction "+IN_12") (pintype "input"))
      (node (ref "IC1") (pin "3") (pinfunction "+IN_3") (pintype "input"))
      (node (ref "IC1") (pin "5") (pinfunction "+IN_5") (pintype "input"))
      (node (ref "IC10") (pin "8") (pinfunction "GND_8") (pintype "power_in"))
      (node (ref "IC11") (pin "12") (pinfunction "+IN_12") (pintype "input"))
      (node (ref "IC11") (pin "3") (pinfunction "+IN_3") (pintype "input"))
      (node (ref "IC11") (pin "5") (pinfunction "+IN_5") (pintype "input"))
      (node (ref "IC12") (pin "12") (pinfunction "+IN_12") (pintype "input"))
      (node (ref "IC12") (pin "3") (pinfunction "+IN_3") (pintype "input"))
      (node (ref "IC12") (pin "5") (pinfunction "+IN_5") (pintype "input"))
      (node (ref "IC2") (pin "12") (pinfunction "+IN_12") (pintype "input"))
      (node (ref "IC2") (pin "3") (pinfunction "+IN_3") (pintype "input"))
      (node (ref "IC2") (pin "5") (pinfunction "+IN_5") (pintype "input"))
      (node (ref "IC3") (pin "8") (pinfunction "GND_8") (pintype "power_in"))
      (node (ref "IC4") (pin "12") (pinfunction "+IN_12") (pintype "input"))
      (node (ref "IC4") (pin "3") (pinfunction "+IN_3") (pintype "input"))
      (node (ref "IC4") (pin "5") (pinfunction "+IN_5") (pintype "input"))
      (node (ref "IC5") (pin "12") (pinfunction "+IN_12") (pintype "input"))
      (node (ref "IC5") (pin "3") (pinfunction "+IN_3") (pintype "input"))
      (node (ref "IC5") (pin "5") (pinfunction "+IN_5") (pintype "input"))
      (node (ref "IC6") (pin "2") (pinfunction "A_2") (pintype "passive"))
      (node (ref "IC7") (pin "1") (pinfunction "C_1") (pintype "passive"))
      (node (ref "IC8") (pin "12") (pinfunction "+IN_12") (pintype "input"))
      (node (ref "IC8") (pin "3") (pinfunction "+IN_3") (pintype "input"))
      (node (ref "IC8") (pin "5") (pinfunction "+IN_5") (pintype "input"))
      (node (ref "IC9") (pin "12") (pinfunction "+IN_12") (pintype "input"))
      (node (ref "IC9") (pin "3") (pinfunction "+IN_3") (pintype "input"))
      (node (ref "IC9") (pin "5") (pinfunction "+IN_5") (pintype "input"))
      (node (ref "J1") (pin "P1") (pinfunction "1_P1") (pintype "passive"))
      (node (ref "J10") (pin "P1") (pinfunction "1_P1") (pintype "passive"))
      (node (ref "J11") (pin "P1") (pinfunction "1_P1") (pintype "passive"))
      (node (ref "J12") (pin "P1") (pinfunction "1_P1") (pintype "passive"))
      (node (ref "J12") (pin "P2") (pinfunction "2_P2") (pintype "passive"))
      (node (ref "J2") (pin "P1") (pinfunction "1_P1") (pintype "passive"))
      (node (ref "J3") (pin "P1") (pinfunction "1_P1") (pintype "passive"))
      (node (ref "J3") (pin "P2") (pinfunction "2_P2") (pintype "passive"))
      (node (ref "J4") (pin "P1") (pinfunction "1_P1") (pintype "passive"))
      (node (ref "J5") (pin "P1") (pinfunction "1_P1") (pintype "passive"))
      (node (ref "J6") (pin "P1") (pinfunction "1_P1") (pintype "passive"))
      (node (ref "J6") (pin "P2") (pinfunction "2_P2") (pintype "passive"))
      (node (ref "J7") (pin "P1") (pinfunction "1_P1") (pintype "passive"))
      (node (ref "J8") (pin "P1") (pinfunction "1_P1") (pintype "passive"))
      (node (ref "J9") (pin "P1") (pinfunction "1_P1") (pintype "passive"))
      (node (ref "J9") (pin "P2") (pinfunction "2_P2") (pintype "passive"))
      (node (ref "JP5") (pin "3") (pinfunction "3_3") (pintype "passive"))
      (node (ref "JP5") (pin "4") (pinfunction "4_4") (pintype "passive"))
      (node (ref "JP5") (pin "5") (pinfunction "5_5") (pintype "passive"))
      (node (ref "JP5") (pin "6") (pinfunction "6_6") (pintype "passive"))
      (node (ref "JP5") (pin "7") (pinfunction "7_7") (pintype "passive"))
      (node (ref "JP5") (pin "8") (pinfunction "8_8") (pintype "passive"))
      (node (ref "R108") (pin "2") (pinfunction "2_2") (pintype "passive"))
      (node (ref "R110") (pin "2") (pinfunction "2_2") (pintype "passive"))
      (node (ref "R113") (pin "2") (pinfunction "2_2") (pintype "passive"))
      (node (ref "R12") (pin "2") (pinfunction "2_2") (pintype "passive"))
      (node (ref "R15") (pin "2") (pinfunction "2_2") (pintype "passive"))
      (node (ref "R18") (pin "2") (pinfunction "2_2") (pintype "passive"))
      (node (ref "R21") (pin "2") (pinfunction "2_2") (pintype "passive"))
      (node (ref "R35") (pin "2") (pinfunction "2_2") (pintype "passive"))
      (node (ref "R36") (pin "P$3") (pinfunction "A_P$3") (pintype "passive"))
      (node (ref "R4") (pin "P$3") (pinfunction "A_P$3") (pintype "passive"))
      (node (ref "R48") (pin "2") (pinfunction "2_2") (pintype "passive"))
      (node (ref "R52") (pin "2") (pinfunction "2_2") (pintype "passive"))
      (node (ref "R53") (pin "2") (pinfunction "2_2") (pintype "passive"))
      (node (ref "R64") (pin "P$3") (pinfunction "A_P$3") (pintype "passive"))
      (node (ref "R72") (pin "2") (pinfunction "2_2") (pintype "passive"))
      (node (ref "R75") (pin "2") (pinfunction "2_2") (pintype "passive"))
      (node (ref "R77") (pin "2") (pinfunction "2_2") (pintype "passive"))
      (node (ref "R80") (pin "2") (pinfunction "2_2") (pintype "passive"))
      (node (ref "R96") (pin "2") (pinfunction "2_2") (pintype "passive"))
      (node (ref "R97") (pin "P$3") (pinfunction "A_P$3") (pintype "passive"))
    )
    (net (code "7") (name "Net-(C12-Pad1)") (class "Default")
      (node (ref "C12") (pin "1") (pinfunction "1_1") (pintype "passive"))
      (node (ref "R26") (pin "1") (pinfunction "1_1") (pintype "passive"))
    )
    (net (code "8") (name "Net-(C13-Pad1)") (class "Default")
      (node (ref "C13") (pin "1") (pinfunction "1_1") (pintype "passive"))
      (node (ref "R27") (pin "1") (pinfunction "1_1") (pintype "passive"))
    )
    (net (code "9") (name "Net-(C14-Pad1)") (class "Default")
      (node (ref "C14") (pin "1") (pinfunction "1_1") (pintype "passive"))
      (node (ref "R33") (pin "1") (pinfunction "1_1") (pintype "passive"))
    )
    (net (code "10") (name "Net-(C15-Pad1)") (class "Default")
      (node (ref "C15") (pin "1") (pinfunction "1_1") (pintype "passive"))
      (node (ref "R32") (pin "1") (pinfunction "1_1") (pintype "passive"))
    )
    (net (code "11") (name "Net-(C37-Pad1)") (class "Default")
      (node (ref "C37") (pin "1") (pinfunction "1_1") (pintype "passive"))
      (node (ref "R87") (pin "1") (pinfunction "1_1") (pintype "passive"))
    )
    (net (code "12") (name "Net-(C38-Pad1)") (class "Default")
      (node (ref "C38") (pin "1") (pinfunction "1_1") (pintype "passive"))
      (node (ref "R88") (pin "1") (pinfunction "1_1") (pintype "passive"))
    )
    (net (code "13") (name "Net-(C39-Pad1)") (class "Default")
      (node (ref "C39") (pin "1") (pinfunction "1_1") (pintype "passive"))
      (node (ref "R94") (pin "1") (pinfunction "1_1") (pintype "passive"))
    )
    (net (code "14") (name "Net-(C40-Pad1)") (class "Default")
      (node (ref "C40") (pin "1") (pinfunction "1_1") (pintype "passive"))
      (node (ref "R93") (pin "1") (pinfunction "1_1") (pintype "passive"))
    )
    (net (code "15") (name "Net-(D2-PadA)") (class "Default")
      (node (ref "D2") (pin "A") (pinfunction "A_A") (pintype "passive"))
      (node (ref "JP5") (pin "1") (pinfunction "1_1") (pintype "passive"))
      (node (ref "JP5") (pin "2") (pinfunction "2_2") (pintype "passive"))
    )
    (net (code "16") (name "Net-(D2-PadC)") (class "Default")
      (node (ref "D2") (pin "C") (pinfunction "C_C") (pintype "passive"))
      (node (ref "L1") (pin "2") (pinfunction "2_2") (pintype "passive"))
    )
    (net (code "17") (name "Net-(IC1A--IN)") (class "Default")
      (node (ref "IC1") (pin "2") (pinfunction "-IN_2") (pintype "input"))
      (node (ref "IC3") (pin "13") (pinfunction "OUT_13") (pintype "output"))
      (node (ref "R7") (pin "2") (pinfunction "2_2") (pintype "passive"))
    )
    (net (code "18") (name "Net-(IC1A-OUT)") (class "Default")
      (node (ref "IC1") (pin "1") (pinfunction "OUT_1") (pintype "output"))
      (node (ref "R13") (pin "2") (pinfunction "2_2") (pintype "passive"))
      (node (ref "R7") (pin "1") (pinfunction "1_1") (pintype "passive"))
    )
    (net (code "19") (name "Net-(IC1B--IN)") (class "Default")
      (node (ref "C9") (pin "1") (pinfunction "1_1") (pintype "passive"))
      (node (ref "IC1") (pin "6") (pinfunction "-IN_6") (pintype "input"))
      (node (ref "R13") (pin "1") (pinfunction "1_1") (pintype "passive"))
      (node (ref "R14") (pin "2") (pinfunction "2_2") (pintype "passive"))
      (node (ref "R23") (pin "1") (pinfunction "1_1") (pintype "passive"))
    )
    (net (code "20") (name "Net-(IC1B-OUT)") (class "Default")
      (node (ref "C9") (pin "2") (pinfunction "2_2") (pintype "passive"))
      (node (ref "IC1") (pin "7") (pinfunction "OUT_7") (pintype "output"))
      (node (ref "R14") (pin "1") (pinfunction "1_1") (pintype "passive"))
      (node (ref "R17") (pin "2") (pinfunction "2_2") (pintype "passive"))
      (node (ref "R24") (pin "2") (pinfunction "2_2") (pintype "passive"))
    )
    (net (code "21") (name "Net-(IC1C-+IN)") (class "Default")
      (node (ref "IC1") (pin "10") (pinfunction "+IN_10") (pintype "input"))
      (node (ref "R18") (pin "1") (pinfunction "1_1") (pintype "passive"))
      (node (ref "R24") (pin "1") (pinfunction "1_1") (pintype "passive"))
    )
    (net (code "22") (name "Net-(IC1C--IN)") (class "Default")
      (node (ref "IC1") (pin "9") (pinfunction "-IN_9") (pintype "input"))
      (node (ref "LED1") (pin "A") (pinfunction "A_A") (pintype "passive"))
      (node (ref "R15") (pin "1") (pinfunction "1_1") (pintype "passive"))
    )
    (net (code "23") (name "Net-(IC1C-OUT)") (class "Default")
      (node (ref "IC1") (pin "8") (pinfunction "OUT_8") (pintype "output"))
      (node (ref "LED1") (pin "K") (pinfunction "C_K") (pintype "passive"))
    )
    (net (code "24") (name "Net-(IC1D--IN)") (class "Default")
      (node (ref "IC1") (pin "13") (pinfunction "-IN_13") (pintype "input"))
      (node (ref "R10") (pin "1") (pinfunction "1_1") (pintype "passive"))
      (node (ref "R8") (pin "2") (pinfunction "2_2") (pintype "passive"))
    )
    (net (code "25") (name "Net-(IC2A--IN)") (class "Default")
      (node (ref "C6") (pin "2") (pinfunction "2_2") (pintype "passive"))
      (node (ref "IC2") (pin "2") (pinfunction "-IN_2") (pintype "input"))
      (node (ref "R1") (pin "1") (pinfunction "1_1") (pintype "passive"))
      (node (ref "R2") (pin "1") (pinfunction "1_1") (pintype "passive"))
      (node (ref "R4") (pin "P$1") (pinfunction "E_P$1") (pintype "passive"))
      (node (ref "R5") (pin "P$3") (pinfunction "A_P$3") (pintype "passive"))
      (node (ref "R6") (pin "2") (pinfunction "2_2") (pintype "passive"))
    )
    (net (code "26") (name "Net-(IC2A-OUT)") (class "Default")
      (node (ref "C6") (pin "1") (pinfunction "1_1") (pintype "passive"))
      (node (ref "IC2") (pin "1") (pinfunction "OUT_1") (pintype "output"))
      (node (ref "R22") (pin "2") (pinfunction "2_2") (pintype "passive"))
      (node (ref "R23") (pin "2") (pinfunction "2_2") (pintype "passive"))
      (node (ref "R29") (pin "2") (pinfunction "2_2") (pintype "passive"))
      (node (ref "R6") (pin "1") (pinfunction "1_1") (pintype "passive"))
    )
    (net (code "27") (name "Net-(IC2B--IN)") (class "Default")
      (node (ref "C10") (pin "1") (pinfunction "1_1") (pintype "passive"))
      (node (ref "IC2") (pin "6") (pinfunction "-IN_6") (pintype "input"))
      (node (ref "IC3") (pin "4") (pinfunction "OUT_4") (pintype "output"))
      (node (ref "R19") (pin "1") (pinfunction "1_1") (pintype "passive"))
      (node (ref "R20") (pin "1") (pinfunction "1_1") (pintype "passive"))
    )
    (net (code "28") (name "Net-(IC2B-OUT)") (class "Default")
      (node (ref "C10") (pin "2") (pinfunction "2_2") (pintype "passive"))
      (node (ref "IC2") (pin "7") (pinfunction "OUT_7") (pintype "output"))
      (node (ref "IC3") (pin "14") (pinfunction "CTRL_14") (pintype "input"))
      (node (ref "IC3") (pin "3") (pinfunction "CTRL_3") (pintype "input"))
    )
    (net (code "29") (name "Net-(IC2C-+IN)") (class "Default")
      (node (ref "IC2") (pin "10") (pinfunction "+IN_10") (pintype "input"))
      (node (ref "R12") (pin "1") (pinfunction "1_1") (pintype "passive"))
      (node (ref "R22") (pin "1") (pinfunction "1_1") (pintype "passive"))
    )
    (net (code "30") (name "Net-(IC2C--IN)") (class "Default")
      (node (ref "IC2") (pin "9") (pinfunction "-IN_9") (pintype "input"))
      (node (ref "LED2") (pin "A") (pinfunction "A_A") (pintype "passive"))
      (node (ref "R21") (pin "1") (pinfunction "1_1") (pintype "passive"))
    )
    (net (code "31") (name "Net-(IC2C-OUT)") (class "Default")
      (node (ref "IC2") (pin "8") (pinfunction "OUT_8") (pintype "output"))
      (node (ref "LED2") (pin "K") (pinfunction "C_K") (pintype "passive"))
    )
    (net (code "32") (name "Net-(IC2D--IN)") (class "Default")
      (node (ref "IC2") (pin "13") (pinfunction "-IN_13") (pintype "input"))
      (node (ref "R5") (pin "P$1") (pinfunction "E_P$1") (pintype "passive"))
      (node (ref "R9") (pin "2") (pinfunction "2_2") (pintype "passive"))
    )
    (net (code "33") (name "Net-(IC2D-OUT)") (class "Default")
      (node (ref "IC2") (pin "14") (pinfunction "OUT_14") (pintype "output"))
      (node (ref "R2") (pin "2") (pinfunction "2_2") (pintype "passive"))
      (node (ref "R9") (pin "1") (pinfunction "1_1") (pintype "passive"))
    )
    (net (code "34") (name "Net-(IC3A-IN)") (class "Default")
      (node (ref "IC3") (pin "2") (pinfunction "IN_2") (pintype "input"))
      (node (ref "R27") (pin "2") (pinfunction "2_2") (pintype "passive"))
      (node (ref "R28") (pin "1") (pinfunction "1_1") (pintype "passive"))
    )
    (net (code "35") (name "Net-(IC3B-CTRL)") (class "Default")
      (node (ref "C19") (pin "2") (pinfunction "2_2") (pintype "passive"))
      (node (ref "IC3") (pin "11") (pinfunction "CTRL_11") (pintype "input"))
      (node (ref "IC3") (pin "6") (pinfunction "CTRL_6") (pintype "input"))
      (node (ref "IC5") (pin "1") (pinfunction "OUT_1") (pintype "output"))
    )
    (net (code "36") (name "Net-(IC3B-IN)") (class "Default")
      (node (ref "IC3") (pin "7") (pinfunction "IN_7") (pintype "input"))
      (node (ref "R31") (pin "1") (pinfunction "1_1") (pintype "passive"))
      (node (ref "R33") (pin "2") (pinfunction "2_2") (pintype "passive"))
    )
    (net (code "37") (name "Net-(IC3B-OUT)") (class "Default")
      (node (ref "C19") (pin "1") (pinfunction "1_1") (pintype "passive"))
      (node (ref "IC3") (pin "5") (pinfunction "OUT_5") (pintype "output"))
      (node (ref "IC5") (pin "2") (pinfunction "-IN_2") (pintype "input"))
      (node (ref "R38") (pin "1") (pinfunction "1_1") (pintype "passive"))
      (node (ref "R39") (pin "1") (pinfunction "1_1") (pintype "passive"))
    )
    (net (code "38") (name "Net-(IC3C-IN)") (class "Default")
      (node (ref "IC3") (pin "10") (pinfunction "IN_10") (pintype "input"))
      (node (ref "R30") (pin "1") (pinfunction "1_1") (pintype "passive"))
      (node (ref "R32") (pin "2") (pinfunction "2_2") (pintype "passive"))
    )
    (net (code "39") (name "Net-(IC3C-OUT)") (class "Default")
      (node (ref "IC3") (pin "12") (pinfunction "OUT_12") (pintype "output"))
      (node (ref "IC4") (pin "2") (pinfunction "-IN_2") (pintype "input"))
      (node (ref "R40") (pin "2") (pinfunction "2_2") (pintype "passive"))
    )
    (net (code "40") (name "Net-(IC3D-IN)") (class "Default")
      (node (ref "IC3") (pin "15") (pinfunction "IN_15") (pintype "input"))
      (node (ref "R26") (pin "2") (pinfunction "2_2") (pintype "passive"))
      (node (ref "R29") (pin "1") (pinfunction "1_1") (pintype "passive"))
    )
    (net (code "41") (name "Net-(IC3E-MODE)") (class "Default")
      (node (ref "IC3") (pin "1") (pinfunction "MODE_1") (pintype "input"))
      (node (ref "R25") (pin "2") (pinfunction "2_2") (pintype "passive"))
    )
    (net (code "42") (name "Net-(IC4A-OUT)") (class "Default")
      (node (ref "IC4") (pin "1") (pinfunction "OUT_1") (pintype "output"))
      (node (ref "R40") (pin "1") (pinfunction "1_1") (pintype "passive"))
      (node (ref "R46") (pin "2") (pinfunction "2_2") (pintype "passive"))
    )
    (net (code "43") (name "Net-(IC4B--IN)") (class "Default")
      (node (ref "C20") (pin "1") (pinfunction "1_1") (pintype "passive"))
      (node (ref "IC4") (pin "6") (pinfunction "-IN_6") (pintype "input"))
      (node (ref "R46") (pin "1") (pinfunction "1_1") (pintype "passive"))
      (node (ref "R47") (pin "2") (pinfunction "2_2") (pintype "passive"))
      (node (ref "R54") (pin "1") (pinfunction "1_1") (pintype "passive"))
      (node (ref "R56") (pin "1") (pinfunction "1_1") (pintype "passive"))
    )
    (net (code "44") (name "Net-(IC4B-OUT)") (class "Default")
      (node (ref "C20") (pin "2") (pinfunction "2_2") (pintype "passive"))
      (node (ref "IC4") (pin "7") (pinfunction "OUT_7") (pintype "output"))
      (node (ref "R47") (pin "1") (pinfunction "1_1") (pintype "passive"))
      (node (ref "R55") (pin "2") (pinfunction "2_2") (pintype "passive"))
      (node (ref "R58") (pin "2") (pinfunction "2_2") (pintype "passive"))
    )
    (net (code "45") (name "Net-(IC4C-+IN)") (class "Default")
      (node (ref "IC4") (pin "10") (pinfunction "+IN_10") (pintype "input"))
      (node (ref "R52") (pin "1") (pinfunction "1_1") (pintype "passive"))
      (node (ref "R58") (pin "1") (pinfunction "1_1") (pintype "passive"))
    )
    (net (code "46") (name "Net-(IC4C--IN)") (class "Default")
      (node (ref "IC4") (pin "9") (pinfunction "-IN_9") (pintype "input"))
      (node (ref "LED3") (pin "A") (pinfunction "A_A") (pintype "passive"))
      (node (ref "R48") (pin "1") (pinfunction "1_1") (pintype "passive"))
    )
    (net (code "47") (name "Net-(IC4C-OUT)") (class "Default")
      (node (ref "IC4") (pin "8") (pinfunction "OUT_8") (pintype "output"))
      (node (ref "LED3") (pin "K") (pinfunction "C_K") (pintype "passive"))
    )
    (net (code "48") (name "Net-(IC4D--IN)") (class "Default")
      (node (ref "IC4") (pin "13") (pinfunction "-IN_13") (pintype "input"))
      (node (ref "R41") (pin "2") (pinfunction "2_2") (pintype "passive"))
      (node (ref "R44") (pin "1") (pinfunction "1_1") (pintype "passive"))
    )
    (net (code "49") (name "Net-(IC5B--IN)") (class "Default")
      (node (ref "C23") (pin "2") (pinfunction "2_2") (pintype "passive"))
      (node (ref "IC5") (pin "6") (pinfunction "-IN_6") (pintype "input"))
      (node (ref "R36") (pin "P$1") (pinfunction "E_P$1") (pintype "passive"))
      (node (ref "R37") (pin "P$3") (pinfunction "A_P$3") (pintype "passive"))
      (node (ref "R50") (pin "1") (pinfunction "1_1") (pintype "passive"))
      (node (ref "R51") (pin "2") (pinfunction "2_2") (pintype "passive"))
      (node (ref "R57") (pin "1") (pinfunction "1_1") (pintype "passive"))
    )
    (net (code "50") (name "Net-(IC5B-OUT)") (class "Default")
      (node (ref "C23") (pin "1") (pinfunction "1_1") (pintype "passive"))
      (node (ref "IC5") (pin "7") (pinfunction "OUT_7") (pintype "output"))
      (node (ref "R30") (pin "2") (pinfunction "2_2") (pintype "passive"))
      (node (ref "R42") (pin "2") (pinfunction "2_2") (pintype "passive"))
      (node (ref "R51") (pin "1") (pinfunction "1_1") (pintype "passive"))
      (node (ref "R54") (pin "2") (pinfunction "2_2") (pintype "passive"))
    )
    (net (code "51") (name "Net-(IC5C-+IN)") (class "Default")
      (node (ref "IC5") (pin "10") (pinfunction "+IN_10") (pintype "input"))
      (node (ref "R35") (pin "1") (pinfunction "1_1") (pintype "passive"))
      (node (ref "R42") (pin "1") (pinfunction "1_1") (pintype "passive"))
    )
    (net (code "52") (name "Net-(IC5C--IN)") (class "Default")
      (node (ref "IC5") (pin "9") (pinfunction "-IN_9") (pintype "input"))
      (node (ref "LED4") (pin "A") (pinfunction "A_A") (pintype "passive"))
      (node (ref "R53") (pin "1") (pinfunction "1_1") (pintype "passive"))
    )
    (net (code "53") (name "Net-(IC5C-OUT)") (class "Default")
      (node (ref "IC5") (pin "8") (pinfunction "OUT_8") (pintype "output"))
      (node (ref "LED4") (pin "K") (pinfunction "C_K") (pintype "passive"))
    )
    (net (code "54") (name "Net-(IC5D--IN)") (class "Default")
      (node (ref "IC5") (pin "13") (pinfunction "-IN_13") (pintype "input"))
      (node (ref "R37") (pin "P$1") (pinfunction "E_P$1") (pintype "passive"))
      (node (ref "R43") (pin "2") (pinfunction "2_2") (pintype "passive"))
    )
    (net (code "55") (name "Net-(IC5D-OUT)") (class "Default")
      (node (ref "IC5") (pin "14") (pinfunction "OUT_14") (pintype "output"))
      (node (ref "R43") (pin "1") (pinfunction "1_1") (pintype "passive"))
      (node (ref "R50") (pin "2") (pinfunction "2_2") (pintype "passive"))
    )
    (net (code "56") (name "Net-(IC8A-OUT)") (class "Default")
      (node (ref "IC8") (pin "1") (pinfunction "OUT_1") (pintype "output"))
      (node (ref "R67") (pin "1") (pinfunction "1_1") (pintype "passive"))
      (node (ref "R73") (pin "2") (pinfunction "2_2") (pintype "passive"))
    )
    (net (code "57") (name "Net-(IC8B--IN)") (class "Default")
      (node (ref "C34") (pin "1") (pinfunction "1_1") (pintype "passive"))
      (node (ref "IC8") (pin "6") (pinfunction "-IN_6") (pintype "input"))
      (node (ref "R73") (pin "1") (pinfunction "1_1") (pintype "passive"))
      (node (ref "R74") (pin "2") (pinfunction "2_2") (pintype "passive"))
      (node (ref "R82") (pin "1") (pinfunction "1_1") (pintype "passive"))
      (node (ref "R83") (pin "1") (pinfunction "1_1") (pintype "passive"))
    )
    (net (code "58") (name "Net-(IC8B-OUT)") (class "Default")
      (node (ref "C34") (pin "2") (pinfunction "2_2") (pintype "passive"))
      (node (ref "IC8") (pin "7") (pinfunction "OUT_7") (pintype "output"))
      (node (ref "R74") (pin "1") (pinfunction "1_1") (pintype "passive"))
      (node (ref "R84") (pin "2") (pinfunction "2_2") (pintype "passive"))
      (node (ref "R85") (pin "2") (pinfunction "2_2") (pintype "passive"))
    )
    (net (code "59") (name "Net-(IC8C-+IN)") (class "Default")
      (node (ref "IC8") (pin "10") (pinfunction "+IN_10") (pintype "input"))
      (node (ref "R77") (pin "1") (pinfunction "1_1") (pintype "passive"))
      (node (ref "R85") (pin "1") (pinfunction "1_1") (pintype "passive"))
    )
    (net (code "60") (name "Net-(IC8C--IN)") (class "Default")
      (node (ref "IC8") (pin "9") (pinfunction "-IN_9") (pintype "input"))
      (node (ref "LED5") (pin "A") (pinfunction "A_A") (pintype "passive"))
      (node (ref "R75") (pin "1") (pinfunction "1_1") (pintype "passive"))
    )
    (net (code "61") (name "Net-(IC8C-OUT)") (class "Default")
      (node (ref "IC8") (pin "8") (pinfunction "OUT_8") (pintype "output"))
      (node (ref "LED5") (pin "K") (pinfunction "C_K") (pintype "passive"))
    )
    (net (code "62") (name "Net-(IC8D--IN)") (class "Default")
      (node (ref "IC8") (pin "13") (pinfunction "-IN_13") (pintype "input"))
      (node (ref "R68") (pin "2") (pinfunction "2_2") (pintype "passive"))
      (node (ref "R70") (pin "1") (pinfunction "1_1") (pintype "passive"))
    )
    (net (code "63") (name "Net-(IC9A--IN)") (class "Default")
      (node (ref "C31") (pin "2") (pinfunction "2_2") (pintype "passive"))
      (node (ref "IC9") (pin "2") (pinfunction "-IN_2") (pintype "input"))
      (node (ref "R61") (pin "1") (pinfunction "1_1") (pintype "passive"))
      (node (ref "R62") (pin "1") (pinfunction "1_1") (pintype "passive"))
      (node (ref "R64") (pin "P$1") (pinfunction "E_P$1") (pintype "passive"))
      (node (ref "R65") (pin "P$3") (pinfunction "A_P$3") (pintype "passive"))
      (node (ref "R66") (pin "2") (pinfunction "2_2") (pintype "passive"))
    )
    (net (code "64") (name "Net-(IC9A-OUT)") (class "Default")
      (node (ref "C31") (pin "1") (pinfunction "1_1") (pintype "passive"))
      (node (ref "IC9") (pin "1") (pinfunction "OUT_1") (pintype "output"))
      (node (ref "R66") (pin "1") (pinfunction "1_1") (pintype "passive"))
      (node (ref "R81") (pin "2") (pinfunction "2_2") (pintype "passive"))
      (node (ref "R83") (pin "2") (pinfunction "2_2") (pintype "passive"))
      (node (ref "R90") (pin "2") (pinfunction "2_2") (pintype "passive"))
    )
    (net (code "65") (name "Net-(IC9C-+IN)") (class "Default")
      (node (ref "IC9") (pin "10") (pinfunction "+IN_10") (pintype "input"))
      (node (ref "R72") (pin "1") (pinfunction "1_1") (pintype "passive"))
      (node (ref "R81") (pin "1") (pinfunction "1_1") (pintype "passive"))
    )
    (net (code "66") (name "Net-(IC9C--IN)") (class "Default")
      (node (ref "IC9") (pin "9") (pinfunction "-IN_9") (pintype "input"))
      (node (ref "LED6") (pin "A") (pinfunction "A_A") (pintype "passive"))
      (node (ref "R80") (pin "1") (pinfunction "1_1") (pintype "passive"))
    )
    (net (code "67") (name "Net-(IC9C-OUT)") (class "Default")
      (node (ref "IC9") (pin "8") (pinfunction "OUT_8") (pintype "output"))
      (node (ref "LED6") (pin "K") (pinfunction "C_K") (pintype "passive"))
    )
    (net (code "68") (name "Net-(IC9D--IN)") (class "Default")
      (node (ref "IC9") (pin "13") (pinfunction "-IN_13") (pintype "input"))
      (node (ref "R65") (pin "P$1") (pinfunction "E_P$1") (pintype "passive"))
      (node (ref "R69") (pin "2") (pinfunction "2_2") (pintype "passive"))
    )
    (net (code "69") (name "Net-(IC9D-OUT)") (class "Default")
      (node (ref "IC9") (pin "14") (pinfunction "OUT_14") (pintype "output"))
      (node (ref "R62") (pin "2") (pinfunction "2_2") (pintype "passive"))
      (node (ref "R69") (pin "1") (pinfunction "1_1") (pintype "passive"))
    )
    (net (code "70") (name "Net-(IC10A-CTRL)") (class "Default")
      (node (ref "C35") (pin "2") (pinfunction "2_2") (pintype "passive"))
      (node (ref "IC10") (pin "14") (pinfunction "CTRL_14") (pintype "input"))
      (node (ref "IC10") (pin "3") (pinfunction "CTRL_3") (pintype "input"))
      (node (ref "IC9") (pin "7") (pinfunction "OUT_7") (pintype "output"))
    )
    (net (code "71") (name "Net-(IC10A-IN)") (class "Default")
      (node (ref "IC10") (pin "2") (pinfunction "IN_2") (pintype "input"))
      (node (ref "R88") (pin "2") (pinfunction "2_2") (pintype "passive"))
      (node (ref "R89") (pin "1") (pinfunction "1_1") (pintype "passive"))
    )
    (net (code "72") (name "Net-(IC10A-OUT)") (class "Default")
      (node (ref "C35") (pin "1") (pinfunction "1_1") (pintype "passive"))
      (node (ref "IC10") (pin "4") (pinfunction "OUT_4") (pintype "output"))
      (node (ref "IC9") (pin "6") (pinfunction "-IN_6") (pintype "input"))
      (node (ref "R78") (pin "1") (pinfunction "1_1") (pintype "passive"))
      (node (ref "R79") (pin "1") (pinfunction "1_1") (pintype "passive"))
    )
    (net (code "73") (name "Net-(IC10B-CTRL)") (class "Default")
      (node (ref "C44") (pin "2") (pinfunction "2_2") (pintype "passive"))
      (node (ref "IC10") (pin "11") (pinfunction "CTRL_11") (pintype "input"))
      (node (ref "IC10") (pin "6") (pinfunction "CTRL_6") (pintype "input"))
      (node (ref "IC12") (pin "1") (pinfunction "OUT_1") (pintype "output"))
    )
    (net (code "74") (name "Net-(IC10B-IN)") (class "Default")
      (node (ref "IC10") (pin "7") (pinfunction "IN_7") (pintype "input"))
      (node (ref "R92") (pin "1") (pinfunction "1_1") (pintype "passive"))
      (node (ref "R94") (pin "2") (pinfunction "2_2") (pintype "passive"))
    )
    (net (code "75") (name "Net-(IC10B-OUT)") (class "Default")
      (node (ref "C44") (pin "1") (pinfunction "1_1") (pintype "passive"))
      (node (ref "IC10") (pin "5") (pinfunction "OUT_5") (pintype "output"))
      (node (ref "IC12") (pin "2") (pinfunction "-IN_2") (pintype "input"))
      (node (ref "R101") (pin "1") (pinfunction "1_1") (pintype "passive"))
      (node (ref "R102") (pin "1") (pinfunction "1_1") (pintype "passive"))
    )
    (net (code "76") (name "Net-(IC10C-IN)") (class "Default")
      (node (ref "IC10") (pin "10") (pinfunction "IN_10") (pintype "input"))
      (node (ref "R91") (pin "1") (pinfunction "1_1") (pintype "passive"))
      (node (ref "R93") (pin "2") (pinfunction "2_2") (pintype "passive"))
    )
    (net (code "77") (name "Net-(IC10C-OUT)") (class "Default")
      (node (ref "IC10") (pin "12") (pinfunction "OUT_12") (pintype "output"))
      (node (ref "IC11") (pin "2") (pinfunction "-IN_2") (pintype "input"))
      (node (ref "R100") (pin "2") (pinfunction "2_2") (pintype "passive"))
    )
    (net (code "78") (name "Net-(IC10D-IN)") (class "Default")
      (node (ref "IC10") (pin "15") (pinfunction "IN_15") (pintype "input"))
      (node (ref "R87") (pin "2") (pinfunction "2_2") (pintype "passive"))
      (node (ref "R90") (pin "1") (pinfunction "1_1") (pintype "passive"))
    )
    (net (code "79") (name "Net-(IC10D-OUT)") (class "Default")
      (node (ref "IC10") (pin "13") (pinfunction "OUT_13") (pintype "output"))
      (node (ref "IC8") (pin "2") (pinfunction "-IN_2") (pintype "input"))
      (node (ref "R67") (pin "2") (pinfunction "2_2") (pintype "passive"))
    )
    (net (code "80") (name "Net-(IC10E-MODE)") (class "Default")
      (node (ref "IC10") (pin "1") (pinfunction "MODE_1") (pintype "input"))
      (node (ref "R86") (pin "2") (pinfunction "2_2") (pintype "passive"))
    )
    (net (code "81") (name "Net-(IC11A-OUT)") (class "Default")
      (node (ref "IC11") (pin "1") (pinfunction "OUT_1") (pintype "output"))
      (node (ref "R100") (pin "1") (pinfunction "1_1") (pintype "passive"))
      (node (ref "R99") (pin "2") (pinfunction "2_2") (pintype "passive"))
    )
    (net (code "82") (name "Net-(IC11B--IN)") (class "Default")
      (node (ref "C45") (pin "1") (pinfunction "1_1") (pintype "passive"))
      (node (ref "IC11") (pin "6") (pinfunction "-IN_6") (pintype "input"))
      (node (ref "R103") (pin "1") (pinfunction "1_1") (pintype "passive"))
      (node (ref "R107") (pin "2") (pinfunction "2_2") (pintype "passive"))
      (node (ref "R114") (pin "1") (pinfunction "1_1") (pintype "passive"))
      (node (ref "R99") (pin "1") (pinfunction "1_1") (pintype "passive"))
    )
    (net (code "83") (name "Net-(IC11B-OUT)") (class "Default")
      (node (ref "C45") (pin "2") (pinfunction "2_2") (pintype "passive"))
      (node (ref "IC11") (pin "7") (pinfunction "OUT_7") (pintype "output"))
      (node (ref "R107") (pin "1") (pinfunction "1_1") (pintype "passive"))
      (node (ref "R115") (pin "2") (pinfunction "2_2") (pintype "passive"))
      (node (ref "R116") (pin "2") (pinfunction "2_2") (pintype "passive"))
    )
    (net (code "84") (name "Net-(IC11C-+IN)") (class "Default")
      (node (ref "IC11") (pin "10") (pinfunction "+IN_10") (pintype "input"))
      (node (ref "R110") (pin "1") (pinfunction "1_1") (pintype "passive"))
      (node (ref "R115") (pin "1") (pinfunction "1_1") (pintype "passive"))
    )
    (net (code "85") (name "Net-(IC11C--IN)") (class "Default")
      (node (ref "IC11") (pin "9") (pinfunction "-IN_9") (pintype "input"))
      (node (ref "LED7") (pin "A") (pinfunction "A_A") (pintype "passive"))
      (node (ref "R108") (pin "1") (pinfunction "1_1") (pintype "passive"))
    )
    (net (code "86") (name "Net-(IC11C-OUT)") (class "Default")
      (node (ref "IC11") (pin "8") (pinfunction "OUT_8") (pintype "output"))
      (node (ref "LED7") (pin "K") (pinfunction "C_K") (pintype "passive"))
    )
    (net (code "87") (name "Net-(IC11D--IN)") (class "Default")
      (node (ref "IC11") (pin "13") (pinfunction "-IN_13") (pintype "input"))
      (node (ref "IC11") (pin "14") (pinfunction "OUT_14") (pintype "output"))
    )
    (net (code "88") (name "Net-(IC12B--IN)") (class "Default")
      (node (ref "C48") (pin "2") (pinfunction "2_2") (pintype "passive"))
      (node (ref "IC12") (pin "6") (pinfunction "-IN_6") (pintype "input"))
      (node (ref "R111") (pin "1") (pinfunction "1_1") (pintype "passive"))
      (node (ref "R112") (pin "2") (pinfunction "2_2") (pintype "passive"))
      (node (ref "R117") (pin "1") (pinfunction "1_1") (pintype "passive"))
      (node (ref "R97") (pin "P$1") (pinfunction "E_P$1") (pintype "passive"))
      (node (ref "R98") (pin "P$3") (pinfunction "A_P$3") (pintype "passive"))
    )
    (net (code "89") (name "Net-(IC12B-OUT)") (class "Default")
      (node (ref "C48") (pin "1") (pinfunction "1_1") (pintype "passive"))
      (node (ref "IC12") (pin "7") (pinfunction "OUT_7") (pintype "output"))
      (node (ref "R103") (pin "2") (pinfunction "2_2") (pintype "passive"))
      (node (ref "R104") (pin "2") (pinfunction "2_2") (pintype "passive"))
      (node (ref "R112") (pin "1") (pinfunction "1_1") (pintype "passive"))
      (node (ref "R91") (pin "2") (pinfunction "2_2") (pintype "passive"))
    )
    (net (code "90") (name "Net-(IC12C-+IN)") (class "Default")
      (node (ref "IC12") (pin "10") (pinfunction "+IN_10") (pintype "input"))
      (node (ref "R104") (pin "1") (pinfunction "1_1") (pintype "passive"))
      (node (ref "R96") (pin "1") (pinfunction "1_1") (pintype "passive"))
    )
    (net (code "91") (name "Net-(IC12C--IN)") (class "Default")
      (node (ref "IC12") (pin "9") (pinfunction "-IN_9") (pintype "input"))
      (node (ref "LED8") (pin "A") (pinfunction "A_A") (pintype "passive"))
      (node (ref "R113") (pin "1") (pinfunction "1_1") (pintype "passive"))
    )
    (net (code "92") (name "Net-(IC12C-OUT)") (class "Default")
      (node (ref "IC12") (pin "8") (pinfunction "OUT_8") (pintype "output"))
      (node (ref "LED8") (pin "K") (pinfunction "C_K") (pintype "passive"))
    )
    (net (code "93") (name "Net-(IC12D--IN)") (class "Default")
      (node (ref "IC12") (pin "13") (pinfunction "-IN_13") (pintype "input"))
      (node (ref "R105") (pin "2") (pinfunction "2_2") (pintype "passive"))
      (node (ref "R98") (pin "P$1") (pinfunction "E_P$1") (pintype "passive"))
    )
    (net (code "94") (name "Net-(IC12D-OUT)") (class "Default")
      (node (ref "IC12") (pin "14") (pinfunction "OUT_14") (pintype "output"))
      (node (ref "R105") (pin "1") (pinfunction "1_1") (pintype "passive"))
      (node (ref "R111") (pin "2") (pinfunction "2_2") (pintype "passive"))
    )
    (net (code "95") (name "Net-(J1-2)") (class "Default")
      (node (ref "J1") (pin "P2") (pinfunction "2_P2") (pintype "passive"))
      (node (ref "R3") (pin "2") (pinfunction "2_2") (pintype "passive"))
    )
    (net (code "96") (name "Net-(J1-3)") (class "Default")
      (node (ref "J1") (pin "P3") (pinfunction "3_P3") (pintype "passive"))
      (node (ref "R19") (pin "2") (pinfunction "2_2") (pintype "passive"))
    )
    (net (code "97") (name "Net-(J2-2)") (class "Default")
      (node (ref "J2") (pin "P2") (pinfunction "2_P2") (pintype "passive"))
      (node (ref "R10") (pin "2") (pinfunction "2_2") (pintype "passive"))
    )
    (net (code "98") (name "Net-(J2-3)") (class "Default")
      (node (ref "J2") (pin "P3") (pinfunction "3_P3") (pintype "passive"))
      (node (ref "R17") (pin "1") (pinfunction "1_1") (pintype "passive"))
    )
    (net (code "99") (name "Net-(J3-3)") (class "Default")
      (node (ref "J3") (pin "P3") (pinfunction "3_P3") (pintype "passive"))
      (node (ref "R11") (pin "2") (pinfunction "2_2") (pintype "passive"))
    )
    (net (code "100") (name "Net-(J4-2)") (class "Default")
      (node (ref "J4") (pin "P2") (pinfunction "2_P2") (pintype "passive"))
      (node (ref "R34") (pin "2") (pinfunction "2_2") (pintype "passive"))
    )
    (net (code "101") (name "Net-(J4-3)") (class "Default")
      (node (ref "J4") (pin "P3") (pinfunction "3_P3") (pintype "passive"))
      (node (ref "R39") (pin "2") (pinfunction "2_2") (pintype "passive"))
    )
    (net (code "102") (name "Net-(J5-2)") (class "Default")
      (node (ref "J5") (pin "P2") (pinfunction "2_P2") (pintype "passive"))
      (node (ref "R44") (pin "2") (pinfunction "2_2") (pintype "passive"))
    )
    (net (code "103") (name "Net-(J5-3)") (class "Default")
      (node (ref "J5") (pin "P3") (pinfunction "3_P3") (pintype "passive"))
      (node (ref "R55") (pin "1") (pinfunction "1_1") (pintype "passive"))
    )
    (net (code "104") (name "Net-(J6-3)") (class "Default")
      (node (ref "J6") (pin "P3") (pinfunction "3_P3") (pintype "passive"))
      (node (ref "R45") (pin "2") (pinfunction "2_2") (pintype "passive"))
    )
    (net (code "105") (name "Net-(J7-2)") (class "Default")
      (node (ref "J7") (pin "P2") (pinfunction "2_P2") (pintype "passive"))
      (node (ref "R63") (pin "2") (pinfunction "2_2") (pintype "passive"))
    )
    (net (code "106") (name "Net-(J7-3)") (class "Default")
      (node (ref "J7") (pin "P3") (pinfunction "3_P3") (pintype "passive"))
      (node (ref "R78") (pin "2") (pinfunction "2_2") (pintype "passive"))
    )
    (net (code "107") (name "Net-(J8-2)") (class "Default")
      (node (ref "J8") (pin "P2") (pinfunction "2_P2") (pintype "passive"))
      (node (ref "R70") (pin "2") (pinfunction "2_2") (pintype "passive"))
    )
    (net (code "108") (name "Net-(J8-3)") (class "Default")
      (node (ref "J8") (pin "P3") (pinfunction "3_P3") (pintype "passive"))
      (node (ref "R84") (pin "1") (pinfunction "1_1") (pintype "passive"))
    )
    (net (code "109") (name "Net-(J9-3)") (class "Default")
      (node (ref "J9") (pin "P3") (pinfunction "3_P3") (pintype "passive"))
      (node (ref "R71") (pin "2") (pinfunction "2_2") (pintype "passive"))
    )
    (net (code "110") (name "Net-(J10-2)") (class "Default")
      (node (ref "J10") (pin "P2") (pinfunction "2_P2") (pintype "passive"))
      (node (ref "R95") (pin "2") (pinfunction "2_2") (pintype "passive"))
    )
    (net (code "111") (name "Net-(J10-3)") (class "Default")
      (node (ref "J10") (pin "P3") (pinfunction "3_P3") (pintype "passive"))
      (node (ref "R102") (pin "2") (pinfunction "2_2") (pintype "passive"))
    )
    (net (code "112") (name "Net-(J11-3)") (class "Default")
      (node (ref "J11") (pin "P3") (pinfunction "3_P3") (pintype "passive"))
      (node (ref "R116") (pin "1") (pinfunction "1_1") (pintype "passive"))
    )
    (net (code "113") (name "Net-(J12-3)") (class "Default")
      (node (ref "J12") (pin "P3") (pinfunction "3_P3") (pintype "passive"))
      (node (ref "R106") (pin "2") (pinfunction "2_2") (pintype "passive"))
    )
    (net (code "114") (name "Net-(JP5-Pad10)") (class "Default")
      (node (ref "JP5") (pin "10") (pinfunction "10_10") (pintype "passive"))
      (node (ref "JP5") (pin "9") (pinfunction "9_9") (pintype "passive"))
      (node (ref "P1") (pin "2") (pinfunction "2_2") (pintype "bidirectional"))
    )
    (net (code "115") (name "Net-(L2-Pad2)") (class "Default")
      (node (ref "L2") (pin "2") (pinfunction "2_2") (pintype "passive"))
      (node (ref "P1") (pin "1") (pinfunction "1_1") (pintype "bidirectional"))
    )
    (net (code "116") (name "Net-(R4-S)") (class "Default")
      (node (ref "R16") (pin "1") (pinfunction "1_1") (pintype "passive"))
      (node (ref "R4") (pin "P$2") (pinfunction "S_P$2") (pintype "passive"))
    )
    (net (code "117") (name "Net-(R5-S)") (class "Default")
      (node (ref "R11") (pin "1") (pinfunction "1_1") (pintype "passive"))
      (node (ref "R5") (pin "P$2") (pinfunction "S_P$2") (pintype "passive"))
    )
    (net (code "118") (name "Net-(R36-S)") (class "Default")
      (node (ref "R36") (pin "P$2") (pinfunction "S_P$2") (pintype "passive"))
      (node (ref "R49") (pin "1") (pinfunction "1_1") (pintype "passive"))
    )
    (net (code "119") (name "Net-(R37-S)") (class "Default")
      (node (ref "R37") (pin "P$2") (pinfunction "S_P$2") (pintype "passive"))
      (node (ref "R45") (pin "1") (pinfunction "1_1") (pintype "passive"))
    )
    (net (code "120") (name "Net-(R64-S)") (class "Default")
      (node (ref "R64") (pin "P$2") (pinfunction "S_P$2") (pintype "passive"))
      (node (ref "R76") (pin "1") (pinfunction "1_1") (pintype "passive"))
    )
    (net (code "121") (name "Net-(R65-S)") (class "Default")
      (node (ref "R65") (pin "P$2") (pinfunction "S_P$2") (pintype "passive"))
      (node (ref "R71") (pin "1") (pinfunction "1_1") (pintype "passive"))
    )
    (net (code "122") (name "Net-(R97-S)") (class "Default")
      (node (ref "R109") (pin "1") (pinfunction "1_1") (pintype "passive"))
      (node (ref "R97") (pin "P$2") (pinfunction "S_P$2") (pintype "passive"))
    )
    (net (code "123") (name "Net-(R98-S)") (class "Default")
      (node (ref "R106") (pin "1") (pinfunction "1_1") (pintype "passive"))
      (node (ref "R98") (pin "P$2") (pinfunction "S_P$2") (pintype "passive"))
    )
    (net (code "124") (name "VCC") (class "Default")
      (node (ref "C11") (pin "1") (pinfunction "1_1") (pintype "passive"))
      (node (ref "C18") (pin "1") (pinfunction "1_1") (pintype "passive"))
      (node (ref "C2") (pin "+") (pinfunction "+_+") (pintype "passive"))
      (node (ref "C21") (pin "1") (pinfunction "1_1") (pintype "passive"))
      (node (ref "C24") (pin "1") (pinfunction "1_1") (pintype "passive"))
      (node (ref "C30") (pin "1") (pinfunction "1_1") (pintype "passive"))
      (node (ref "C32") (pin "1") (pinfunction "1_1") (pintype "passive"))
      (node (ref "C36") (pin "1") (pinfunction "1_1") (pintype "passive"))
      (node (ref "C43") (pin "1") (pinfunction "1_1") (pintype "passive"))
      (node (ref "C46") (pin "1") (pinfunction "1_1") (pintype "passive"))
      (node (ref "C5") (pin "1") (pinfunction "1_1") (pintype "passive"))
      (node (ref "C7") (pin "1") (pinfunction "1_1") (pintype "passive"))
      (node (ref "IC1") (pin "4") (pinfunction "V+_4") (pintype "power_in"))
      (node (ref "IC10") (pin "16") (pinfunction "V+_16") (pintype "power_in"))
      (node (ref "IC11") (pin "4") (pinfunction "V+_4") (pintype "power_in"))
      (node (ref "IC12") (pin "4") (pinfunction "V+_4") (pintype "power_in"))
      (node (ref "IC2") (pin "4") (pinfunction "V+_4") (pintype "power_in"))
      (node (ref "IC3") (pin "16") (pinfunction "V+_16") (pintype "power_in"))
      (node (ref "IC4") (pin "4") (pinfunction "V+_4") (pintype "power_in"))
      (node (ref "IC5") (pin "4") (pinfunction "V+_4") (pintype "power_in"))
      (node (ref "IC8") (pin "4") (pinfunction "V+_4") (pintype "power_in"))
      (node (ref "IC9") (pin "4") (pinfunction "V+_4") (pintype "power_in"))
      (node (ref "L1") (pin "1") (pinfunction "1_1") (pintype "passive"))
      (node (ref "R25") (pin "1") (pinfunction "1_1") (pintype "passive"))
      (node (ref "R59") (pin "1") (pinfunction "1_1") (pintype "passive"))
      (node (ref "R86") (pin "1") (pinfunction "1_1") (pintype "passive"))
    )
    (net (code "125") (name "VEE") (class "Default")
      (node (ref "C1") (pin "-") (pinfunction "-_-") (pintype "passive"))
      (node (ref "C16") (pin "2") (pinfunction "2_2") (pintype "passive"))
      (node (ref "C17") (pin "2") (pinfunction "2_2") (pintype "passive"))
      (node (ref "C22") (pin "2") (pinfunction "2_2") (pintype "passive"))
      (node (ref "C25") (pin "1") (pinfunction "1_1") (pintype "passive"))
      (node (ref "C29") (pin "2") (pinfunction "2_2") (pintype "passive"))
      (node (ref "C33") (pin "2") (pinfunction "2_2") (pintype "passive"))
      (node (ref "C4") (pin "2") (pinfunction "2_2") (pintype "passive"))
      (node (ref "C41") (pin "2") (pinfunction "2_2") (pintype "passive"))
      (node (ref "C42") (pin "2") (pinfunction "2_2") (pintype "passive"))
      (node (ref "C47") (pin "2") (pinfunction "2_2") (pintype "passive"))
      (node (ref "C8") (pin "2") (pinfunction "2_2") (pintype "passive"))
      (node (ref "D1") (pin "A") (pinfunction "A_A") (pintype "passive"))
      (node (ref "IC1") (pin "11") (pinfunction "V-_11") (pintype "power_in"))
      (node (ref "IC10") (pin "9") (pinfunction "V-_9") (pintype "power_in"))
      (node (ref "IC11") (pin "11") (pinfunction "V-_11") (pintype "power_in"))
      (node (ref "IC12") (pin "11") (pinfunction "V-_11") (pintype "power_in"))
      (node (ref "IC2") (pin "11") (pinfunction "V-_11") (pintype "power_in"))
      (node (ref "IC3") (pin "9") (pinfunction "V-_9") (pintype "power_in"))
      (node (ref "IC4") (pin "11") (pinfunction "V-_11") (pintype "power_in"))
      (node (ref "IC5") (pin "11") (pinfunction "V-_11") (pintype "power_in"))
      (node (ref "IC8") (pin "11") (pinfunction "V-_11") (pintype "power_in"))
      (node (ref "IC9") (pin "11") (pinfunction "V-_11") (pintype "power_in"))
      (node (ref "L2") (pin "1") (pinfunction "1_1") (pintype "passive"))
      (node (ref "R60") (pin "1") (pinfunction "1_1") (pintype "passive"))
    )
    (net (code "126") (name "unconnected-(J11-2-PadP2)") (class "Default")
      (node (ref "J11") (pin "P2") (pinfunction "2_P2") (pintype "passive"))
    )
  )
)
